# 56_ch_sample-and-hold_card_v1_2.net
KiCad netlist of a schematic drawn in EAGLE
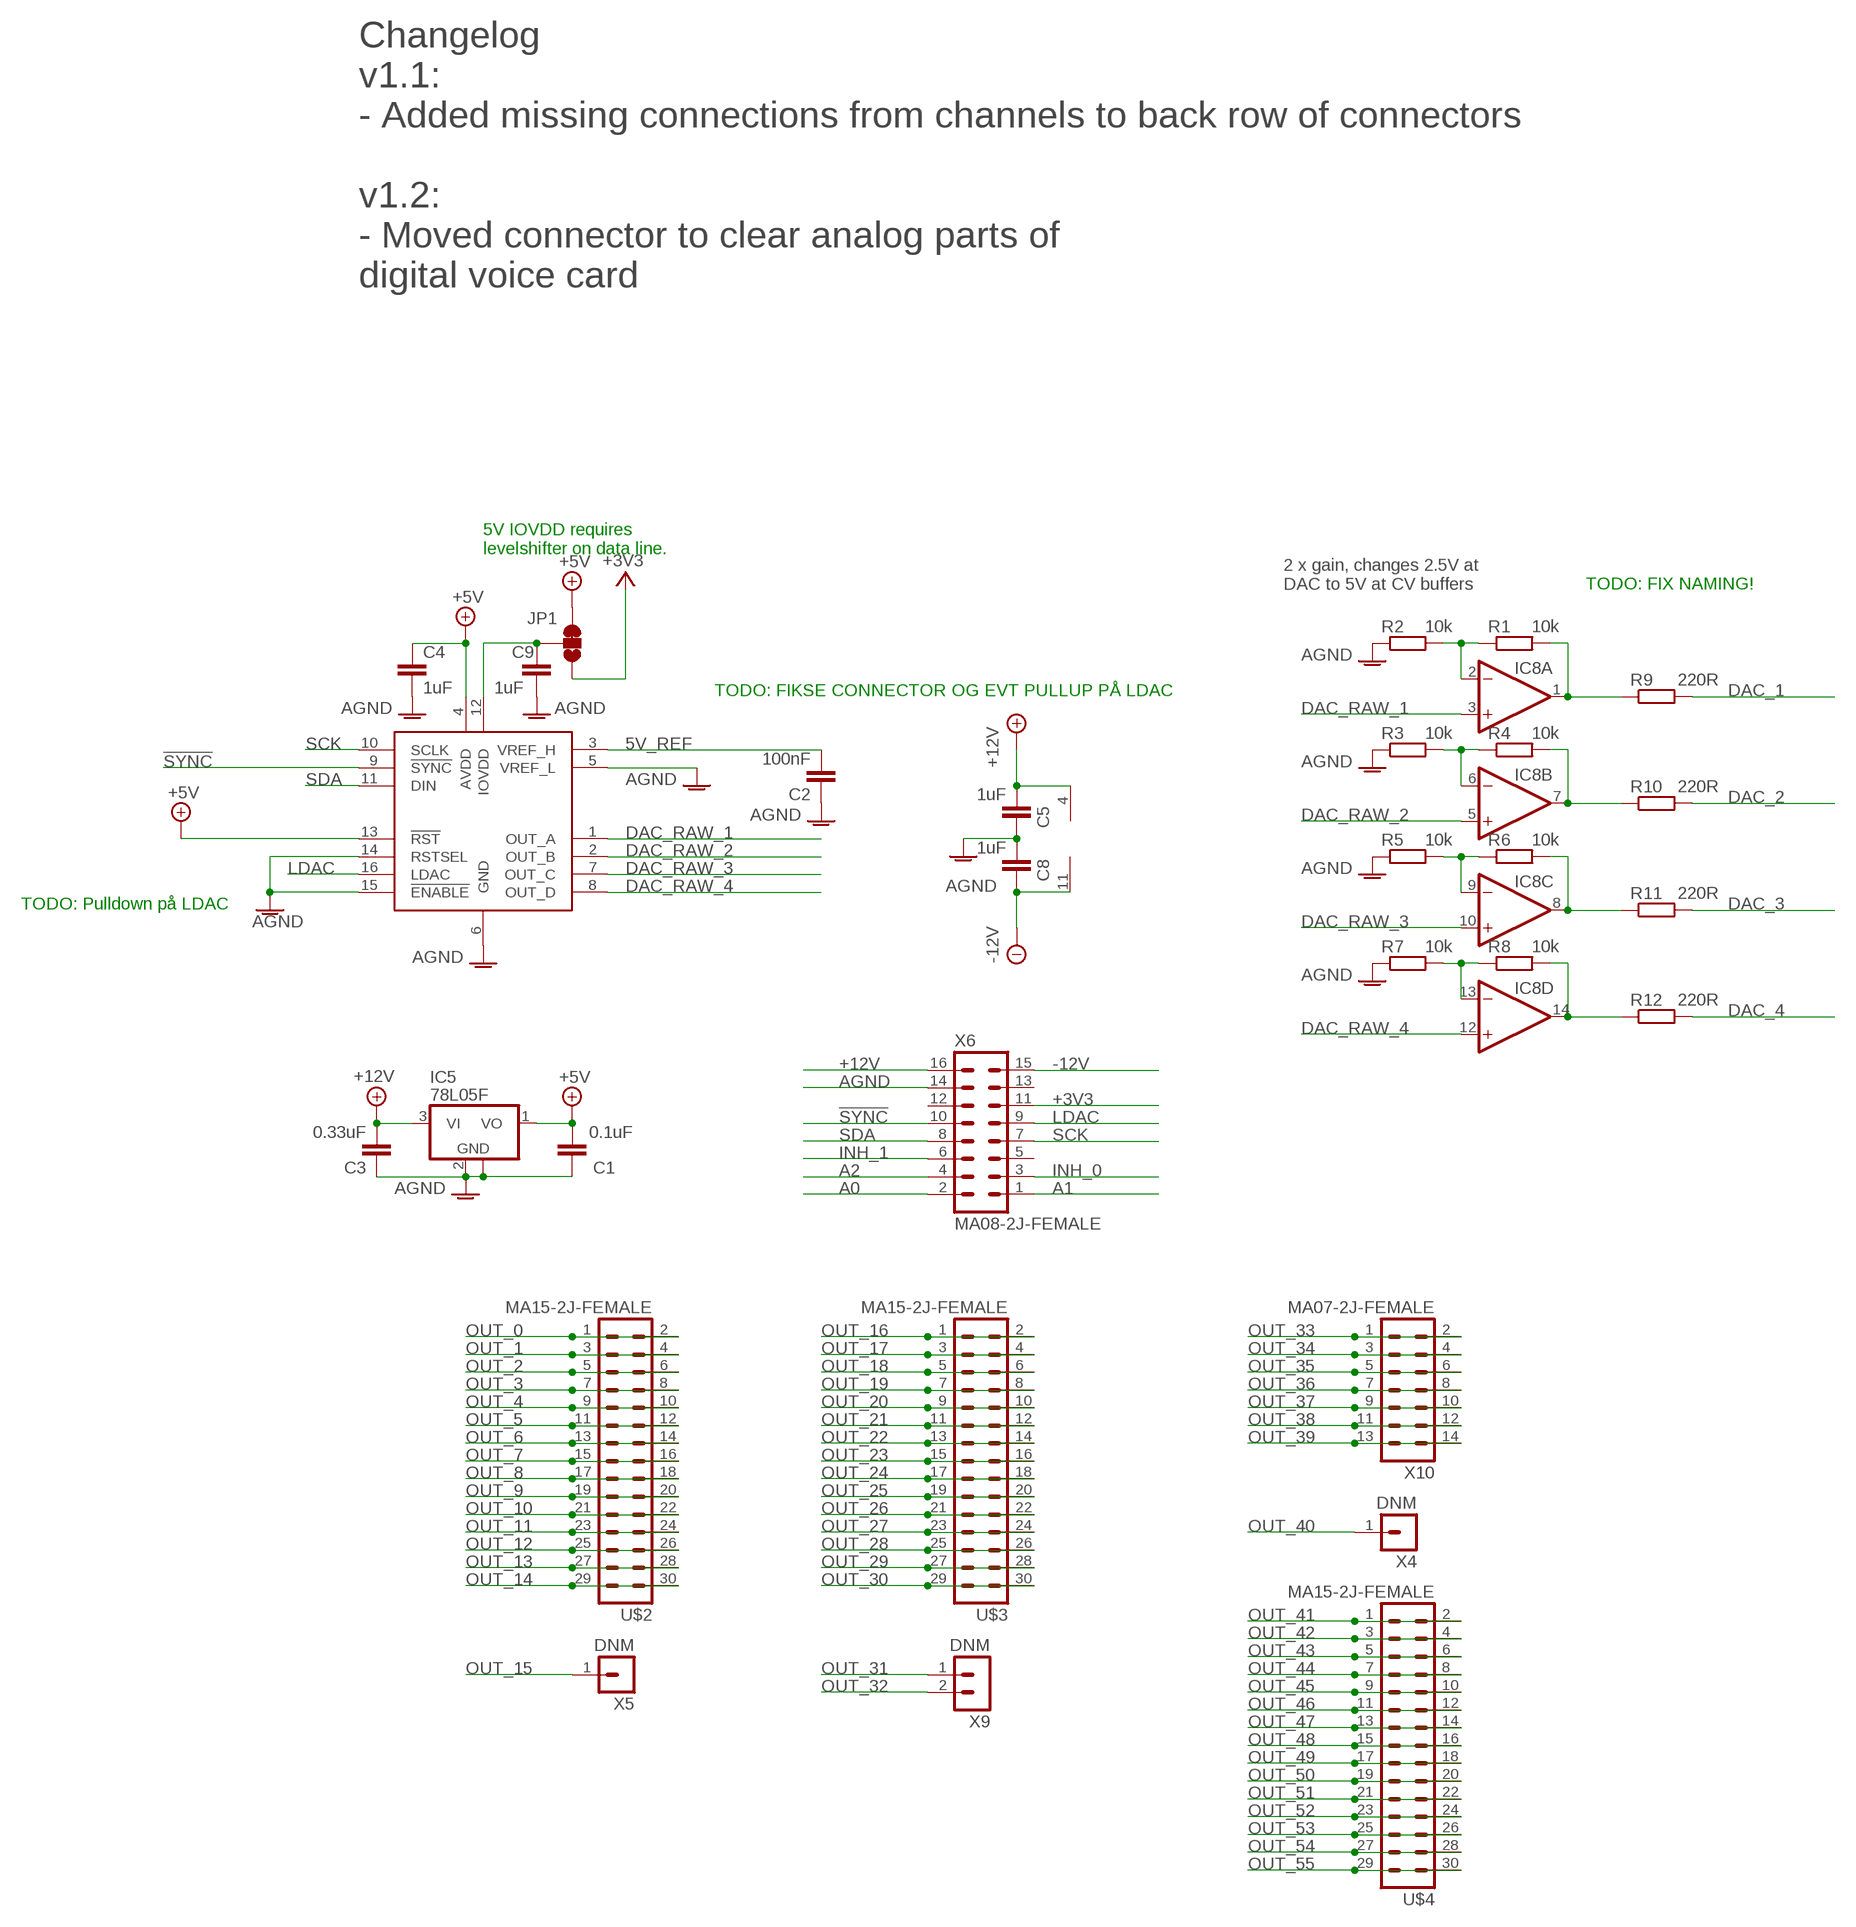
[diagram p0: schematic, sheet 1]
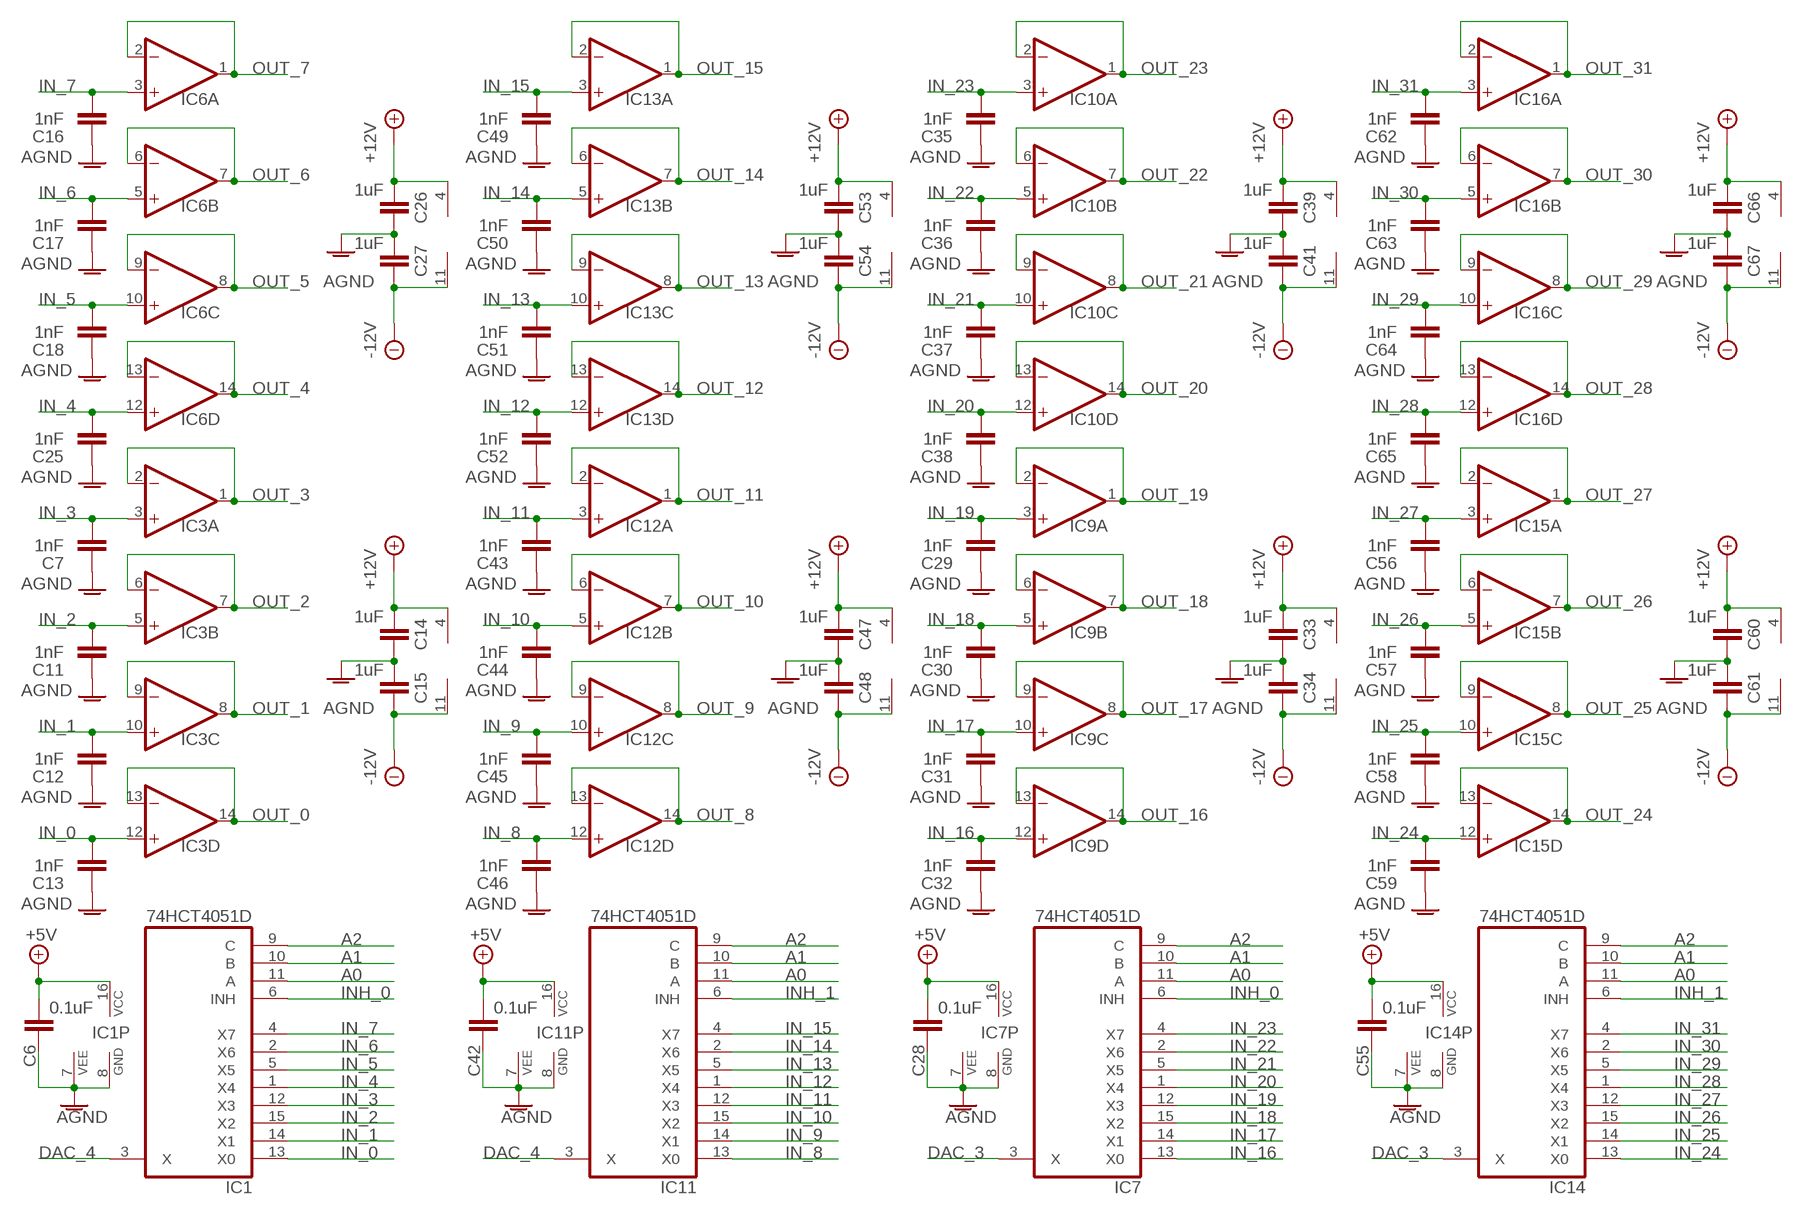
[diagram p1: schematic, sheet 2]
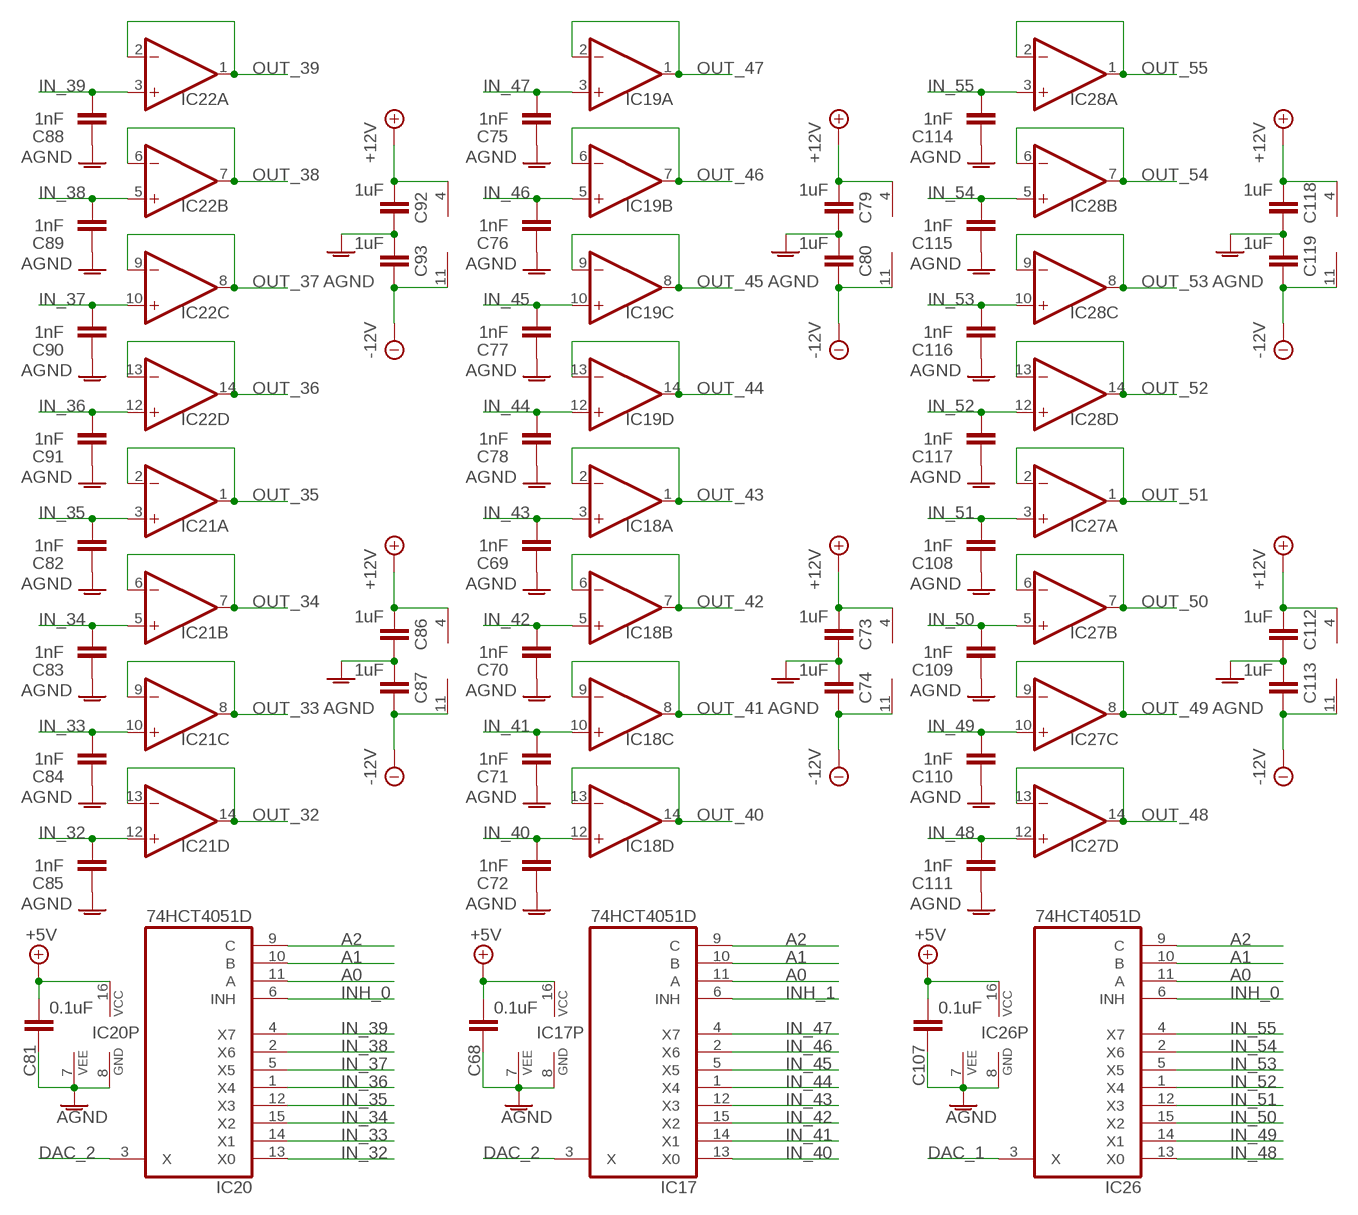
[diagram p2: schematic, sheet 3]

(export (version "E")
  (design (tool "Eeschema 10.0.6"))
  (components
    (comp (ref "C1")
      (value "0.1uF")
      (footprint "eagle-import:C0603")
      (libsource (lib "eagle-import") (part "C-EUC0603"))
    )
    (comp (ref "C2")
      (value "100nF")
      (footprint "eagle-import:C0603")
      (libsource (lib "eagle-import") (part "C-EUC0603"))
    )
    (comp (ref "C3")
      (value "0.33uF")
      (footprint "eagle-import:C0603")
      (libsource (lib "eagle-import") (part "C-EUC0603"))
    )
    (comp (ref "C4")
      (value "1uF")
      (footprint "eagle-import:C0402-J")
      (libsource (lib "eagle-import") (part "C-EU-J0402"))
    )
    (comp (ref "C5")
      (value "1uF")
      (footprint "eagle-import:C0402-J")
      (libsource (lib "eagle-import") (part "C-EU-J0402"))
    )
    (comp (ref "C8")
      (value "1uF")
      (footprint "eagle-import:C0402-J")
      (libsource (lib "eagle-import") (part "C-EU-J0402"))
    )
    (comp (ref "C9")
      (value "1uF")
      (footprint "eagle-import:C0402-J")
      (libsource (lib "eagle-import") (part "C-EU-J0402"))
    )
    (comp (ref "IC2")
      (value "DAC8565F")
      (footprint "eagle-import:DIL16-FM-CON")
      (libsource (lib "eagle-import") (part "DAC8565F"))
    )
    (comp (ref "IC5")
      (value "78L05F")
      (footprint "eagle-import:SOT89")
      (libsource (lib "eagle-import") (part "78LF05"))
    )
    (comp (ref "IC8")
      (value "TL074JT")
      (footprint "eagle-import:TSSOP14J")
      (libsource (lib "eagle-import") (part "TL074JT"))
    )
    (comp (ref "JP1")
      (value "JUMPER-SMT_3_1-NC_TRACE_NO-SILK_DNM")
      (footprint "eagle-import:SMT-JUMPER_3_1-NC_TRACE_NO-SILK")
      (libsource (lib "eagle-import") (part "JUMPER-SMT_3_1-NC_TRACE_NO-SILK"))
    )
    (comp (ref "R1")
      (value "10k")
      (footprint "eagle-import:R0603")
      (libsource (lib "eagle-import") (part "R-EU_R0603"))
    )
    (comp (ref "R2")
      (value "10k")
      (footprint "eagle-import:R0603")
      (libsource (lib "eagle-import") (part "R-EU_R0603"))
    )
    (comp (ref "R3")
      (value "10k")
      (footprint "eagle-import:R0603")
      (libsource (lib "eagle-import") (part "R-EU_R0603"))
    )
    (comp (ref "R4")
      (value "10k")
      (footprint "eagle-import:R0603")
      (libsource (lib "eagle-import") (part "R-EU_R0603"))
    )
    (comp (ref "R5")
      (value "10k")
      (footprint "eagle-import:R0603")
      (libsource (lib "eagle-import") (part "R-EU_R0603"))
    )
    (comp (ref "R6")
      (value "10k")
      (footprint "eagle-import:R0603")
      (libsource (lib "eagle-import") (part "R-EU_R0603"))
    )
    (comp (ref "R7")
      (value "10k")
      (footprint "eagle-import:R0603")
      (libsource (lib "eagle-import") (part "R-EU_R0603"))
    )
    (comp (ref "R8")
      (value "10k")
      (footprint "eagle-import:R0603")
      (libsource (lib "eagle-import") (part "R-EU_R0603"))
    )
    (comp (ref "R9")
      (value "220R")
      (footprint "eagle-import:R0603")
      (libsource (lib "eagle-import") (part "R-EU_R0603"))
    )
    (comp (ref "R10")
      (value "220R")
      (footprint "eagle-import:R0603")
      (libsource (lib "eagle-import") (part "R-EU_R0603"))
    )
    (comp (ref "R11")
      (value "220R")
      (footprint "eagle-import:R0603")
      (libsource (lib "eagle-import") (part "R-EU_R0603"))
    )
    (comp (ref "R12")
      (value "220R")
      (footprint "eagle-import:R0603")
      (libsource (lib "eagle-import") (part "R-EU_R0603"))
    )
    (comp (ref "U$2")
      (value "MA15-2J-FEMALE")
      (footprint "eagle-import:MA15-2J")
      (libsource (lib "eagle-import") (part "MA15-2J"))
    )
    (comp (ref "U$3")
      (value "MA15-2J-FEMALE")
      (footprint "eagle-import:MA15-2J")
      (libsource (lib "eagle-import") (part "MA15-2J"))
    )
    (comp (ref "U$4")
      (value "MA15-2J-FEMALE")
      (footprint "eagle-import:MA15-2J")
      (libsource (lib "eagle-import") (part "MA15-2J"))
    )
    (comp (ref "X4")
      (value "DNM")
      (footprint "eagle-import:MA01N-1J")
      (libsource (lib "eagle-import") (part "MA01-1JN"))
    )
    (comp (ref "X5")
      (value "DNM")
      (footprint "eagle-import:MA01N-1J")
      (libsource (lib "eagle-import") (part "MA01-1JN"))
    )
    (comp (ref "X6")
      (value "MA08-2J-FEMALE")
      (footprint "eagle-import:MA08-2J")
      (libsource (lib "eagle-import") (part "MA08-2J"))
    )
    (comp (ref "X9")
      (value "DNM")
      (footprint "eagle-import:MA02N-1J")
      (libsource (lib "eagle-import") (part "MA02-1JN"))
    )
    (comp (ref "X10")
      (value "MA07-2J-FEMALE")
      (footprint "eagle-import:MA07-2J")
      (libsource (lib "eagle-import") (part "MA07-2J"))
    )
    (comp (ref "C68")
      (value "0.1uF")
      (footprint "eagle-import:C0402-J")
      (libsource (lib "eagle-import") (part "C-EU-J0402"))
    )
    (comp (ref "C69")
      (value "1nF")
      (footprint "eagle-import:C0603-J")
      (libsource (lib "eagle-import") (part "C-EU-J0603"))
    )
    (comp (ref "C70")
      (value "1nF")
      (footprint "eagle-import:C0603-J")
      (libsource (lib "eagle-import") (part "C-EU-J0603"))
    )
    (comp (ref "C71")
      (value "1nF")
      (footprint "eagle-import:C0603-J")
      (libsource (lib "eagle-import") (part "C-EU-J0603"))
    )
    (comp (ref "C72")
      (value "1nF")
      (footprint "eagle-import:C0603-J")
      (libsource (lib "eagle-import") (part "C-EU-J0603"))
    )
    (comp (ref "C73")
      (value "1uF")
      (footprint "eagle-import:C0402-J")
      (libsource (lib "eagle-import") (part "C-EU-J0402"))
    )
    (comp (ref "C74")
      (value "1uF")
      (footprint "eagle-import:C0402-J")
      (libsource (lib "eagle-import") (part "C-EU-J0402"))
    )
    (comp (ref "C75")
      (value "1nF")
      (footprint "eagle-import:C0603-J")
      (libsource (lib "eagle-import") (part "C-EU-J0603"))
    )
    (comp (ref "C76")
      (value "1nF")
      (footprint "eagle-import:C0603-J")
      (libsource (lib "eagle-import") (part "C-EU-J0603"))
    )
    (comp (ref "C77")
      (value "1nF")
      (footprint "eagle-import:C0603-J")
      (libsource (lib "eagle-import") (part "C-EU-J0603"))
    )
    (comp (ref "C78")
      (value "1nF")
      (footprint "eagle-import:C0603-J")
      (libsource (lib "eagle-import") (part "C-EU-J0603"))
    )
    (comp (ref "C79")
      (value "1uF")
      (footprint "eagle-import:C0402-J")
      (libsource (lib "eagle-import") (part "C-EU-J0402"))
    )
    (comp (ref "C80")
      (value "1uF")
      (footprint "eagle-import:C0402-J")
      (libsource (lib "eagle-import") (part "C-EU-J0402"))
    )
    (comp (ref "C81")
      (value "0.1uF")
      (footprint "eagle-import:C0402-J")
      (libsource (lib "eagle-import") (part "C-EU-J0402"))
    )
    (comp (ref "C82")
      (value "1nF")
      (footprint "eagle-import:C0603-J")
      (libsource (lib "eagle-import") (part "C-EU-J0603"))
    )
    (comp (ref "C83")
      (value "1nF")
      (footprint "eagle-import:C0603-J")
      (libsource (lib "eagle-import") (part "C-EU-J0603"))
    )
    (comp (ref "C84")
      (value "1nF")
      (footprint "eagle-import:C0603-J")
      (libsource (lib "eagle-import") (part "C-EU-J0603"))
    )
    (comp (ref "C85")
      (value "1nF")
      (footprint "eagle-import:C0603-J")
      (libsource (lib "eagle-import") (part "C-EU-J0603"))
    )
    (comp (ref "C86")
      (value "1uF")
      (footprint "eagle-import:C0402-J")
      (libsource (lib "eagle-import") (part "C-EU-J0402"))
    )
    (comp (ref "C87")
      (value "1uF")
      (footprint "eagle-import:C0402-J")
      (libsource (lib "eagle-import") (part "C-EU-J0402"))
    )
    (comp (ref "C88")
      (value "1nF")
      (footprint "eagle-import:C0603-J")
      (libsource (lib "eagle-import") (part "C-EU-J0603"))
    )
    (comp (ref "C89")
      (value "1nF")
      (footprint "eagle-import:C0603-J")
      (libsource (lib "eagle-import") (part "C-EU-J0603"))
    )
    (comp (ref "C90")
      (value "1nF")
      (footprint "eagle-import:C0603-J")
      (libsource (lib "eagle-import") (part "C-EU-J0603"))
    )
    (comp (ref "C91")
      (value "1nF")
      (footprint "eagle-import:C0603-J")
      (libsource (lib "eagle-import") (part "C-EU-J0603"))
    )
    (comp (ref "C92")
      (value "1uF")
      (footprint "eagle-import:C0402-J")
      (libsource (lib "eagle-import") (part "C-EU-J0402"))
    )
    (comp (ref "C93")
      (value "1uF")
      (footprint "eagle-import:C0402-J")
      (libsource (lib "eagle-import") (part "C-EU-J0402"))
    )
    (comp (ref "C107")
      (value "0.1uF")
      (footprint "eagle-import:C0402-J")
      (libsource (lib "eagle-import") (part "C-EU-J0402"))
    )
    (comp (ref "C108")
      (value "1nF")
      (footprint "eagle-import:C0603-J")
      (libsource (lib "eagle-import") (part "C-EU-J0603"))
    )
    (comp (ref "C109")
      (value "1nF")
      (footprint "eagle-import:C0603-J")
      (libsource (lib "eagle-import") (part "C-EU-J0603"))
    )
    (comp (ref "C110")
      (value "1nF")
      (footprint "eagle-import:C0603-J")
      (libsource (lib "eagle-import") (part "C-EU-J0603"))
    )
    (comp (ref "C111")
      (value "1nF")
      (footprint "eagle-import:C0603-J")
      (libsource (lib "eagle-import") (part "C-EU-J0603"))
    )
    (comp (ref "C112")
      (value "1uF")
      (footprint "eagle-import:C0402-J")
      (libsource (lib "eagle-import") (part "C-EU-J0402"))
    )
    (comp (ref "C113")
      (value "1uF")
      (footprint "eagle-import:C0402-J")
      (libsource (lib "eagle-import") (part "C-EU-J0402"))
    )
    (comp (ref "C114")
      (value "1nF")
      (footprint "eagle-import:C0603-J")
      (libsource (lib "eagle-import") (part "C-EU-J0603"))
    )
    (comp (ref "C115")
      (value "1nF")
      (footprint "eagle-import:C0603-J")
      (libsource (lib "eagle-import") (part "C-EU-J0603"))
    )
    (comp (ref "C116")
      (value "1nF")
      (footprint "eagle-import:C0603-J")
      (libsource (lib "eagle-import") (part "C-EU-J0603"))
    )
    (comp (ref "C117")
      (value "1nF")
      (footprint "eagle-import:C0603-J")
      (libsource (lib "eagle-import") (part "C-EU-J0603"))
    )
    (comp (ref "C118")
      (value "1uF")
      (footprint "eagle-import:C0402-J")
      (libsource (lib "eagle-import") (part "C-EU-J0402"))
    )
    (comp (ref "C119")
      (value "1uF")
      (footprint "eagle-import:C0402-J")
      (libsource (lib "eagle-import") (part "C-EU-J0402"))
    )
    (comp (ref "IC17")
      (value "74HCT4051D")
      (footprint "eagle-import:SO16")
      (libsource (lib "eagle-import") (part "4051D"))
    )
    (comp (ref "IC18")
      (value "TL074JT")
      (footprint "eagle-import:TSSOP14J")
      (libsource (lib "eagle-import") (part "TL074JT"))
    )
    (comp (ref "IC19")
      (value "TL074JT")
      (footprint "eagle-import:TSSOP14J")
      (libsource (lib "eagle-import") (part "TL074JT"))
    )
    (comp (ref "IC20")
      (value "74HCT4051D")
      (footprint "eagle-import:SO16")
      (libsource (lib "eagle-import") (part "4051D"))
    )
    (comp (ref "IC21")
      (value "TL074JT")
      (footprint "eagle-import:TSSOP14J")
      (libsource (lib "eagle-import") (part "TL074JT"))
    )
    (comp (ref "IC22")
      (value "TL074JT")
      (footprint "eagle-import:TSSOP14J")
      (libsource (lib "eagle-import") (part "TL074JT"))
    )
    (comp (ref "IC26")
      (value "74HCT4051D")
      (footprint "eagle-import:SO16")
      (libsource (lib "eagle-import") (part "4051D"))
    )
    (comp (ref "IC27")
      (value "TL074JT")
      (footprint "eagle-import:TSSOP14J")
      (libsource (lib "eagle-import") (part "TL074JT"))
    )
    (comp (ref "IC28")
      (value "TL074JT")
      (footprint "eagle-import:TSSOP14J")
      (libsource (lib "eagle-import") (part "TL074JT"))
    )
    (comp (ref "C6")
      (value "0.1uF")
      (footprint "eagle-import:C0402-J")
      (libsource (lib "eagle-import") (part "C-EU-J0402"))
    )
    (comp (ref "C7")
      (value "1nF")
      (footprint "eagle-import:C0603-J")
      (libsource (lib "eagle-import") (part "C-EU-J0603"))
    )
    (comp (ref "C11")
      (value "1nF")
      (footprint "eagle-import:C0603-J")
      (libsource (lib "eagle-import") (part "C-EU-J0603"))
    )
    (comp (ref "C12")
      (value "1nF")
      (footprint "eagle-import:C0603-J")
      (libsource (lib "eagle-import") (part "C-EU-J0603"))
    )
    (comp (ref "C13")
      (value "1nF")
      (footprint "eagle-import:C0603-J")
      (libsource (lib "eagle-import") (part "C-EU-J0603"))
    )
    (comp (ref "C14")
      (value "1uF")
      (footprint "eagle-import:C0402-J")
      (libsource (lib "eagle-import") (part "C-EU-J0402"))
    )
    (comp (ref "C15")
      (value "1uF")
      (footprint "eagle-import:C0402-J")
      (libsource (lib "eagle-import") (part "C-EU-J0402"))
    )
    (comp (ref "C16")
      (value "1nF")
      (footprint "eagle-import:C0603-J")
      (libsource (lib "eagle-import") (part "C-EU-J0603"))
    )
    (comp (ref "C17")
      (value "1nF")
      (footprint "eagle-import:C0603-J")
      (libsource (lib "eagle-import") (part "C-EU-J0603"))
    )
    (comp (ref "C18")
      (value "1nF")
      (footprint "eagle-import:C0603-J")
      (libsource (lib "eagle-import") (part "C-EU-J0603"))
    )
    (comp (ref "C25")
      (value "1nF")
      (footprint "eagle-import:C0603-J")
      (libsource (lib "eagle-import") (part "C-EU-J0603"))
    )
    (comp (ref "C26")
      (value "1uF")
      (footprint "eagle-import:C0402-J")
      (libsource (lib "eagle-import") (part "C-EU-J0402"))
    )
    (comp (ref "C27")
      (value "1uF")
      (footprint "eagle-import:C0402-J")
      (libsource (lib "eagle-import") (part "C-EU-J0402"))
    )
    (comp (ref "C28")
      (value "0.1uF")
      (footprint "eagle-import:C0402-J")
      (libsource (lib "eagle-import") (part "C-EU-J0402"))
    )
    (comp (ref "C29")
      (value "1nF")
      (footprint "eagle-import:C0603-J")
      (libsource (lib "eagle-import") (part "C-EU-J0603"))
    )
    (comp (ref "C30")
      (value "1nF")
      (footprint "eagle-import:C0603-J")
      (libsource (lib "eagle-import") (part "C-EU-J0603"))
    )
    (comp (ref "C31")
      (value "1nF")
      (footprint "eagle-import:C0603-J")
      (libsource (lib "eagle-import") (part "C-EU-J0603"))
    )
    (comp (ref "C32")
      (value "1nF")
      (footprint "eagle-import:C0603-J")
      (libsource (lib "eagle-import") (part "C-EU-J0603"))
    )
    (comp (ref "C33")
      (value "1uF")
      (footprint "eagle-import:C0402-J")
      (libsource (lib "eagle-import") (part "C-EU-J0402"))
    )
    (comp (ref "C34")
      (value "1uF")
      (footprint "eagle-import:C0402-J")
      (libsource (lib "eagle-import") (part "C-EU-J0402"))
    )
    (comp (ref "C35")
      (value "1nF")
      (footprint "eagle-import:C0603-J")
      (libsource (lib "eagle-import") (part "C-EU-J0603"))
    )
    (comp (ref "C36")
      (value "1nF")
      (footprint "eagle-import:C0603-J")
      (libsource (lib "eagle-import") (part "C-EU-J0603"))
    )
    (comp (ref "C37")
      (value "1nF")
      (footprint "eagle-import:C0603-J")
      (libsource (lib "eagle-import") (part "C-EU-J0603"))
    )
    (comp (ref "C38")
      (value "1nF")
      (footprint "eagle-import:C0603-J")
      (libsource (lib "eagle-import") (part "C-EU-J0603"))
    )
    (comp (ref "C39")
      (value "1uF")
      (footprint "eagle-import:C0402-J")
      (libsource (lib "eagle-import") (part "C-EU-J0402"))
    )
    (comp (ref "C41")
      (value "1uF")
      (footprint "eagle-import:C0402-J")
      (libsource (lib "eagle-import") (part "C-EU-J0402"))
    )
    (comp (ref "C42")
      (value "0.1uF")
      (footprint "eagle-import:C0402-J")
      (libsource (lib "eagle-import") (part "C-EU-J0402"))
    )
    (comp (ref "C43")
      (value "1nF")
      (footprint "eagle-import:C0603-J")
      (libsource (lib "eagle-import") (part "C-EU-J0603"))
    )
    (comp (ref "C44")
      (value "1nF")
      (footprint "eagle-import:C0603-J")
      (libsource (lib "eagle-import") (part "C-EU-J0603"))
    )
    (comp (ref "C45")
      (value "1nF")
      (footprint "eagle-import:C0603-J")
      (libsource (lib "eagle-import") (part "C-EU-J0603"))
    )
    (comp (ref "C46")
      (value "1nF")
      (footprint "eagle-import:C0603-J")
      (libsource (lib "eagle-import") (part "C-EU-J0603"))
    )
    (comp (ref "C47")
      (value "1uF")
      (footprint "eagle-import:C0402-J")
      (libsource (lib "eagle-import") (part "C-EU-J0402"))
    )
    (comp (ref "C48")
      (value "1uF")
      (footprint "eagle-import:C0402-J")
      (libsource (lib "eagle-import") (part "C-EU-J0402"))
    )
    (comp (ref "C49")
      (value "1nF")
      (footprint "eagle-import:C0603-J")
      (libsource (lib "eagle-import") (part "C-EU-J0603"))
    )
    (comp (ref "C50")
      (value "1nF")
      (footprint "eagle-import:C0603-J")
      (libsource (lib "eagle-import") (part "C-EU-J0603"))
    )
    (comp (ref "C51")
      (value "1nF")
      (footprint "eagle-import:C0603-J")
      (libsource (lib "eagle-import") (part "C-EU-J0603"))
    )
    (comp (ref "C52")
      (value "1nF")
      (footprint "eagle-import:C0603-J")
      (libsource (lib "eagle-import") (part "C-EU-J0603"))
    )
    (comp (ref "C53")
      (value "1uF")
      (footprint "eagle-import:C0402-J")
      (libsource (lib "eagle-import") (part "C-EU-J0402"))
    )
    (comp (ref "C54")
      (value "1uF")
      (footprint "eagle-import:C0402-J")
      (libsource (lib "eagle-import") (part "C-EU-J0402"))
    )
    (comp (ref "C55")
      (value "0.1uF")
      (footprint "eagle-import:C0402-J")
      (libsource (lib "eagle-import") (part "C-EU-J0402"))
    )
    (comp (ref "C56")
      (value "1nF")
      (footprint "eagle-import:C0603-J")
      (libsource (lib "eagle-import") (part "C-EU-J0603"))
    )
    (comp (ref "C57")
      (value "1nF")
      (footprint "eagle-import:C0603-J")
      (libsource (lib "eagle-import") (part "C-EU-J0603"))
    )
    (comp (ref "C58")
      (value "1nF")
      (footprint "eagle-import:C0603-J")
      (libsource (lib "eagle-import") (part "C-EU-J0603"))
    )
    (comp (ref "C59")
      (value "1nF")
      (footprint "eagle-import:C0603-J")
      (libsource (lib "eagle-import") (part "C-EU-J0603"))
    )
    (comp (ref "C60")
      (value "1uF")
      (footprint "eagle-import:C0402-J")
      (libsource (lib "eagle-import") (part "C-EU-J0402"))
    )
    (comp (ref "C61")
      (value "1uF")
      (footprint "eagle-import:C0402-J")
      (libsource (lib "eagle-import") (part "C-EU-J0402"))
    )
    (comp (ref "C62")
      (value "1nF")
      (footprint "eagle-import:C0603-J")
      (libsource (lib "eagle-import") (part "C-EU-J0603"))
    )
    (comp (ref "C63")
      (value "1nF")
      (footprint "eagle-import:C0603-J")
      (libsource (lib "eagle-import") (part "C-EU-J0603"))
    )
    (comp (ref "C64")
      (value "1nF")
      (footprint "eagle-import:C0603-J")
      (libsource (lib "eagle-import") (part "C-EU-J0603"))
    )
    (comp (ref "C65")
      (value "1nF")
      (footprint "eagle-import:C0603-J")
      (libsource (lib "eagle-import") (part "C-EU-J0603"))
    )
    (comp (ref "C66")
      (value "1uF")
      (footprint "eagle-import:C0402-J")
      (libsource (lib "eagle-import") (part "C-EU-J0402"))
    )
    (comp (ref "C67")
      (value "1uF")
      (footprint "eagle-import:C0402-J")
      (libsource (lib "eagle-import") (part "C-EU-J0402"))
    )
    (comp (ref "IC1")
      (value "74HCT4051D")
      (footprint "eagle-import:SO16")
      (libsource (lib "eagle-import") (part "4051D"))
    )
    (comp (ref "IC3")
      (value "TL074JT")
      (footprint "eagle-import:TSSOP14J")
      (libsource (lib "eagle-import") (part "TL074JT"))
    )
    (comp (ref "IC6")
      (value "TL074JT")
      (footprint "eagle-import:TSSOP14J")
      (libsource (lib "eagle-import") (part "TL074JT"))
    )
    (comp (ref "IC7")
      (value "74HCT4051D")
      (footprint "eagle-import:SO16")
      (libsource (lib "eagle-import") (part "4051D"))
    )
    (comp (ref "IC9")
      (value "TL074JT")
      (footprint "eagle-import:TSSOP14J")
      (libsource (lib "eagle-import") (part "TL074JT"))
    )
    (comp (ref "IC10")
      (value "TL074JT")
      (footprint "eagle-import:TSSOP14J")
      (libsource (lib "eagle-import") (part "TL074JT"))
    )
    (comp (ref "IC11")
      (value "74HCT4051D")
      (footprint "eagle-import:SO16")
      (libsource (lib "eagle-import") (part "4051D"))
    )
    (comp (ref "IC12")
      (value "TL074JT")
      (footprint "eagle-import:TSSOP14J")
      (libsource (lib "eagle-import") (part "TL074JT"))
    )
    (comp (ref "IC13")
      (value "TL074JT")
      (footprint "eagle-import:TSSOP14J")
      (libsource (lib "eagle-import") (part "TL074JT"))
    )
    (comp (ref "IC14")
      (value "74HCT4051D")
      (footprint "eagle-import:SO16")
      (libsource (lib "eagle-import") (part "4051D"))
    )
    (comp (ref "IC15")
      (value "TL074JT")
      (footprint "eagle-import:TSSOP14J")
      (libsource (lib "eagle-import") (part "TL074JT"))
    )
    (comp (ref "IC16")
      (value "TL074JT")
      (footprint "eagle-import:TSSOP14J")
      (libsource (lib "eagle-import") (part "TL074JT"))
    )
  )
  (nets
    (net (code "1") (name "+3V3") (class "Default")
      (node (ref "JP1") (pin "1") (pinfunction "1_1") (pintype "passive"))
      (node (ref "X6") (pin "11") (pinfunction "11_11") (pintype "passive"))
    )
    (net (code "2") (name "+5V") (class "Default")
      (node (ref "C1") (pin "2") (pinfunction "2_2") (pintype "passive"))
      (node (ref "C107") (pin "2") (pinfunction "2_2") (pintype "passive"))
      (node (ref "C28") (pin "2") (pinfunction "2_2") (pintype "passive"))
      (node (ref "C4") (pin "1") (pinfunction "1_1") (pintype "passive"))
      (node (ref "C42") (pin "2") (pinfunction "2_2") (pintype "passive"))
      (node (ref "C55") (pin "2") (pinfunction "2_2") (pintype "passive"))
      (node (ref "C6") (pin "2") (pinfunction "2_2") (pintype "passive"))
      (node (ref "C68") (pin "2") (pinfunction "2_2") (pintype "passive"))
      (node (ref "C81") (pin "2") (pinfunction "2_2") (pintype "passive"))
      (node (ref "IC1") (pin "16") (pinfunction "VCC_16") (pintype "power_in"))
      (node (ref "IC11") (pin "16") (pinfunction "VCC_16") (pintype "power_in"))
      (node (ref "IC14") (pin "16") (pinfunction "VCC_16") (pintype "power_in"))
      (node (ref "IC17") (pin "16") (pinfunction "VCC_16") (pintype "power_in"))
      (node (ref "IC2") (pin "13") (pinfunction "~{RST}_13") (pintype "bidirectional"))
      (node (ref "IC2") (pin "4") (pinfunction "AVDD_4") (pintype "power_in"))
      (node (ref "IC20") (pin "16") (pinfunction "VCC_16") (pintype "power_in"))
      (node (ref "IC26") (pin "16") (pinfunction "VCC_16") (pintype "power_in"))
      (node (ref "IC5") (pin "1") (pinfunction "VO_1") (pintype "passive"))
      (node (ref "IC7") (pin "16") (pinfunction "VCC_16") (pintype "power_in"))
      (node (ref "JP1") (pin "3") (pinfunction "3_3") (pintype "passive"))
    )
    (net (code "3") (name "+12V") (class "Default")
      (node (ref "C112") (pin "1") (pinfunction "1_1") (pintype "passive"))
      (node (ref "C118") (pin "1") (pinfunction "1_1") (pintype "passive"))
      (node (ref "C14") (pin "1") (pinfunction "1_1") (pintype "passive"))
      (node (ref "C26") (pin "1") (pinfunction "1_1") (pintype "passive"))
      (node (ref "C3") (pin "2") (pinfunction "2_2") (pintype "passive"))
      (node (ref "C33") (pin "1") (pinfunction "1_1") (pintype "passive"))
      (node (ref "C39") (pin "1") (pinfunction "1_1") (pintype "passive"))
      (node (ref "C47") (pin "1") (pinfunction "1_1") (pintype "passive"))
      (node (ref "C5") (pin "1") (pinfunction "1_1") (pintype "passive"))
      (node (ref "C53") (pin "1") (pinfunction "1_1") (pintype "passive"))
      (node (ref "C60") (pin "1") (pinfunction "1_1") (pintype "passive"))
      (node (ref "C66") (pin "1") (pinfunction "1_1") (pintype "passive"))
      (node (ref "C73") (pin "1") (pinfunction "1_1") (pintype "passive"))
      (node (ref "C79") (pin "1") (pinfunction "1_1") (pintype "passive"))
      (node (ref "C86") (pin "1") (pinfunction "1_1") (pintype "passive"))
      (node (ref "C92") (pin "1") (pinfunction "1_1") (pintype "passive"))
      (node (ref "IC10") (pin "4") (pinfunction "V+_4") (pintype "power_in"))
      (node (ref "IC12") (pin "4") (pinfunction "V+_4") (pintype "power_in"))
      (node (ref "IC13") (pin "4") (pinfunction "V+_4") (pintype "power_in"))
      (node (ref "IC15") (pin "4") (pinfunction "V+_4") (pintype "power_in"))
      (node (ref "IC16") (pin "4") (pinfunction "V+_4") (pintype "power_in"))
      (node (ref "IC18") (pin "4") (pinfunction "V+_4") (pintype "power_in"))
      (node (ref "IC19") (pin "4") (pinfunction "V+_4") (pintype "power_in"))
      (node (ref "IC21") (pin "4") (pinfunction "V+_4") (pintype "power_in"))
      (node (ref "IC22") (pin "4") (pinfunction "V+_4") (pintype "power_in"))
      (node (ref "IC27") (pin "4") (pinfunction "V+_4") (pintype "power_in"))
      (node (ref "IC28") (pin "4") (pinfunction "V+_4") (pintype "power_in"))
      (node (ref "IC3") (pin "4") (pinfunction "V+_4") (pintype "power_in"))
      (node (ref "IC5") (pin "3") (pinfunction "VI_3") (pintype "input"))
      (node (ref "IC6") (pin "4") (pinfunction "V+_4") (pintype "power_in"))
      (node (ref "IC8") (pin "4") (pinfunction "V+_4") (pintype "power_in"))
      (node (ref "IC9") (pin "4") (pinfunction "V+_4") (pintype "power_in"))
      (node (ref "X6") (pin "16") (pinfunction "16_16") (pintype "passive"))
    )
    (net (code "4") (name "-12V") (class "Default")
      (node (ref "C113") (pin "2") (pinfunction "2_2") (pintype "passive"))
      (node (ref "C119") (pin "2") (pinfunction "2_2") (pintype "passive"))
      (node (ref "C15") (pin "2") (pinfunction "2_2") (pintype "passive"))
      (node (ref "C27") (pin "2") (pinfunction "2_2") (pintype "passive"))
      (node (ref "C34") (pin "2") (pinfunction "2_2") (pintype "passive"))
      (node (ref "C41") (pin "2") (pinfunction "2_2") (pintype "passive"))
      (node (ref "C48") (pin "2") (pinfunction "2_2") (pintype "passive"))
      (node (ref "C54") (pin "2") (pinfunction "2_2") (pintype "passive"))
      (node (ref "C61") (pin "2") (pinfunction "2_2") (pintype "passive"))
      (node (ref "C67") (pin "2") (pinfunction "2_2") (pintype "passive"))
      (node (ref "C74") (pin "2") (pinfunction "2_2") (pintype "passive"))
      (node (ref "C8") (pin "2") (pinfunction "2_2") (pintype "passive"))
      (node (ref "C80") (pin "2") (pinfunction "2_2") (pintype "passive"))
      (node (ref "C87") (pin "2") (pinfunction "2_2") (pintype "passive"))
      (node (ref "C93") (pin "2") (pinfunction "2_2") (pintype "passive"))
      (node (ref "IC10") (pin "11") (pinfunction "V-_11") (pintype "power_in"))
      (node (ref "IC12") (pin "11") (pinfunction "V-_11") (pintype "power_in"))
      (node (ref "IC13") (pin "11") (pinfunction "V-_11") (pintype "power_in"))
      (node (ref "IC15") (pin "11") (pinfunction "V-_11") (pintype "power_in"))
      (node (ref "IC16") (pin "11") (pinfunction "V-_11") (pintype "power_in"))
      (node (ref "IC18") (pin "11") (pinfunction "V-_11") (pintype "power_in"))
      (node (ref "IC19") (pin "11") (pinfunction "V-_11") (pintype "power_in"))
      (node (ref "IC21") (pin "11") (pinfunction "V-_11") (pintype "power_in"))
      (node (ref "IC22") (pin "11") (pinfunction "V-_11") (pintype "power_in"))
      (node (ref "IC27") (pin "11") (pinfunction "V-_11") (pintype "power_in"))
      (node (ref "IC28") (pin "11") (pinfunction "V-_11") (pintype "power_in"))
      (node (ref "IC3") (pin "11") (pinfunction "V-_11") (pintype "power_in"))
      (node (ref "IC6") (pin "11") (pinfunction "V-_11") (pintype "power_in"))
      (node (ref "IC8") (pin "11") (pinfunction "V-_11") (pintype "power_in"))
      (node (ref "IC9") (pin "11") (pinfunction "V-_11") (pintype "power_in"))
      (node (ref "X6") (pin "15") (pinfunction "15_15") (pintype "passive"))
    )
    (net (code "5") (name "5V_REF") (class "Default")
      (node (ref "C2") (pin "2") (pinfunction "2_2") (pintype "passive"))
      (node (ref "IC2") (pin "3") (pinfunction "VREF_H_3") (pintype "bidirectional"))
    )
    (net (code "6") (name "A0") (class "Default")
      (node (ref "IC1") (pin "11") (pinfunction "A_11") (pintype "input"))
      (node (ref "IC11") (pin "11") (pinfunction "A_11") (pintype "input"))
      (node (ref "IC14") (pin "11") (pinfunction "A_11") (pintype "input"))
      (node (ref "IC17") (pin "11") (pinfunction "A_11") (pintype "input"))
      (node (ref "IC20") (pin "11") (pinfunction "A_11") (pintype "input"))
      (node (ref "IC26") (pin "11") (pinfunction "A_11") (pintype "input"))
      (node (ref "IC7") (pin "11") (pinfunction "A_11") (pintype "input"))
      (node (ref "X6") (pin "2") (pinfunction "2_2") (pintype "passive"))
    )
    (net (code "7") (name "A1") (class "Default")
      (node (ref "IC1") (pin "10") (pinfunction "B_10") (pintype "input"))
      (node (ref "IC11") (pin "10") (pinfunction "B_10") (pintype "input"))
      (node (ref "IC14") (pin "10") (pinfunction "B_10") (pintype "input"))
      (node (ref "IC17") (pin "10") (pinfunction "B_10") (pintype "input"))
      (node (ref "IC20") (pin "10") (pinfunction "B_10") (pintype "input"))
      (node (ref "IC26") (pin "10") (pinfunction "B_10") (pintype "input"))
      (node (ref "IC7") (pin "10") (pinfunction "B_10") (pintype "input"))
      (node (ref "X6") (pin "1") (pinfunction "1_1") (pintype "passive"))
    )
    (net (code "8") (name "A2") (class "Default")
      (node (ref "IC1") (pin "9") (pinfunction "C_9") (pintype "input"))
      (node (ref "IC11") (pin "9") (pinfunction "C_9") (pintype "input"))
      (node (ref "IC14") (pin "9") (pinfunction "C_9") (pintype "input"))
      (node (ref "IC17") (pin "9") (pinfunction "C_9") (pintype "input"))
      (node (ref "IC20") (pin "9") (pinfunction "C_9") (pintype "input"))
      (node (ref "IC26") (pin "9") (pinfunction "C_9") (pintype "input"))
      (node (ref "IC7") (pin "9") (pinfunction "C_9") (pintype "input"))
      (node (ref "X6") (pin "4") (pinfunction "4_4") (pintype "passive"))
    )
    (net (code "9") (name "AGND") (class "Default")
      (node (ref "C1") (pin "1") (pinfunction "1_1") (pintype "passive"))
      (node (ref "C107") (pin "1") (pinfunction "1_1") (pintype "passive"))
      (node (ref "C108") (pin "1") (pinfunction "1_1") (pintype "passive"))
      (node (ref "C109") (pin "1") (pinfunction "1_1") (pintype "passive"))
      (node (ref "C11") (pin "1") (pinfunction "1_1") (pintype "passive"))
      (node (ref "C110") (pin "1") (pinfunction "1_1") (pintype "passive"))
      (node (ref "C111") (pin "1") (pinfunction "1_1") (pintype "passive"))
      (node (ref "C112") (pin "2") (pinfunction "2_2") (pintype "passive"))
      (node (ref "C113") (pin "1") (pinfunction "1_1") (pintype "passive"))
      (node (ref "C114") (pin "1") (pinfunction "1_1") (pintype "passive"))
      (node (ref "C115") (pin "1") (pinfunction "1_1") (pintype "passive"))
      (node (ref "C116") (pin "1") (pinfunction "1_1") (pintype "passive"))
      (node (ref "C117") (pin "1") (pinfunction "1_1") (pintype "passive"))
      (node (ref "C118") (pin "2") (pinfunction "2_2") (pintype "passive"))
      (node (ref "C119") (pin "1") (pinfunction "1_1") (pintype "passive"))
      (node (ref "C12") (pin "1") (pinfunction "1_1") (pintype "passive"))
      (node (ref "C13") (pin "1") (pinfunction "1_1") (pintype "passive"))
      (node (ref "C14") (pin "2") (pinfunction "2_2") (pintype "passive"))
      (node (ref "C15") (pin "1") (pinfunction "1_1") (pintype "passive"))
      (node (ref "C16") (pin "1") (pinfunction "1_1") (pintype "passive"))
      (node (ref "C17") (pin "1") (pinfunction "1_1") (pintype "passive"))
      (node (ref "C18") (pin "1") (pinfunction "1_1") (pintype "passive"))
      (node (ref "C2") (pin "1") (pinfunction "1_1") (pintype "passive"))
      (node (ref "C25") (pin "1") (pinfunction "1_1") (pintype "passive"))
      (node (ref "C26") (pin "2") (pinfunction "2_2") (pintype "passive"))
      (node (ref "C27") (pin "1") (pinfunction "1_1") (pintype "passive"))
      (node (ref "C28") (pin "1") (pinfunction "1_1") (pintype "passive"))
      (node (ref "C29") (pin "1") (pinfunction "1_1") (pintype "passive"))
      (node (ref "C3") (pin "1") (pinfunction "1_1") (pintype "passive"))
      (node (ref "C30") (pin "1") (pinfunction "1_1") (pintype "passive"))
      (node (ref "C31") (pin "1") (pinfunction "1_1") (pintype "passive"))
      (node (ref "C32") (pin "1") (pinfunction "1_1") (pintype "passive"))
      (node (ref "C33") (pin "2") (pinfunction "2_2") (pintype "passive"))
      (node (ref "C34") (pin "1") (pinfunction "1_1") (pintype "passive"))
      (node (ref "C35") (pin "1") (pinfunction "1_1") (pintype "passive"))
      (node (ref "C36") (pin "1") (pinfunction "1_1") (pintype "passive"))
      (node (ref "C37") (pin "1") (pinfunction "1_1") (pintype "passive"))
      (node (ref "C38") (pin "1") (pinfunction "1_1") (pintype "passive"))
      (node (ref "C39") (pin "2") (pinfunction "2_2") (pintype "passive"))
      (node (ref "C4") (pin "2") (pinfunction "2_2") (pintype "passive"))
      (node (ref "C41") (pin "1") (pinfunction "1_1") (pintype "passive"))
      (node (ref "C42") (pin "1") (pinfunction "1_1") (pintype "passive"))
      (node (ref "C43") (pin "1") (pinfunction "1_1") (pintype "passive"))
      (node (ref "C44") (pin "1") (pinfunction "1_1") (pintype "passive"))
      (node (ref "C45") (pin "1") (pinfunction "1_1") (pintype "passive"))
      (node (ref "C46") (pin "1") (pinfunction "1_1") (pintype "passive"))
      (node (ref "C47") (pin "2") (pinfunction "2_2") (pintype "passive"))
      (node (ref "C48") (pin "1") (pinfunction "1_1") (pintype "passive"))
      (node (ref "C49") (pin "1") (pinfunction "1_1") (pintype "passive"))
      (node (ref "C5") (pin "2") (pinfunction "2_2") (pintype "passive"))
      (node (ref "C50") (pin "1") (pinfunction "1_1") (pintype "passive"))
      (node (ref "C51") (pin "1") (pinfunction "1_1") (pintype "passive"))
      (node (ref "C52") (pin "1") (pinfunction "1_1") (pintype "passive"))
      (node (ref "C53") (pin "2") (pinfunction "2_2") (pintype "passive"))
      (node (ref "C54") (pin "1") (pinfunction "1_1") (pintype "passive"))
      (node (ref "C55") (pin "1") (pinfunction "1_1") (pintype "passive"))
      (node (ref "C56") (pin "1") (pinfunction "1_1") (pintype "passive"))
      (node (ref "C57") (pin "1") (pinfunction "1_1") (pintype "passive"))
      (node (ref "C58") (pin "1") (pinfunction "1_1") (pintype "passive"))
      (node (ref "C59") (pin "1") (pinfunction "1_1") (pintype "passive"))
      (node (ref "C6") (pin "1") (pinfunction "1_1") (pintype "passive"))
      (node (ref "C60") (pin "2") (pinfunction "2_2") (pintype "passive"))
      (node (ref "C61") (pin "1") (pinfunction "1_1") (pintype "passive"))
      (node (ref "C62") (pin "1") (pinfunction "1_1") (pintype "passive"))
      (node (ref "C63") (pin "1") (pinfunction "1_1") (pintype "passive"))
      (node (ref "C64") (pin "1") (pinfunction "1_1") (pintype "passive"))
      (node (ref "C65") (pin "1") (pinfunction "1_1") (pintype "passive"))
      (node (ref "C66") (pin "2") (pinfunction "2_2") (pintype "passive"))
      (node (ref "C67") (pin "1") (pinfunction "1_1") (pintype "passive"))
      (node (ref "C68") (pin "1") (pinfunction "1_1") (pintype "passive"))
      (node (ref "C69") (pin "1") (pinfunction "1_1") (pintype "passive"))
      (node (ref "C7") (pin "1") (pinfunction "1_1") (pintype "passive"))
      (node (ref "C70") (pin "1") (pinfunction "1_1") (pintype "passive"))
      (node (ref "C71") (pin "1") (pinfunction "1_1") (pintype "passive"))
      (node (ref "C72") (pin "1") (pinfunction "1_1") (pintype "passive"))
      (node (ref "C73") (pin "2") (pinfunction "2_2") (pintype "passive"))
      (node (ref "C74") (pin "1") (pinfunction "1_1") (pintype "passive"))
      (node (ref "C75") (pin "1") (pinfunction "1_1") (pintype "passive"))
      (node (ref "C76") (pin "1") (pinfunction "1_1") (pintype "passive"))
      (node (ref "C77") (pin "1") (pinfunction "1_1") (pintype "passive"))
      (node (ref "C78") (pin "1") (pinfunction "1_1") (pintype "passive"))
      (node (ref "C79") (pin "2") (pinfunction "2_2") (pintype "passive"))
      (node (ref "C8") (pin "1") (pinfunction "1_1") (pintype "passive"))
      (node (ref "C80") (pin "1") (pinfunction "1_1") (pintype "passive"))
      (node (ref "C81") (pin "1") (pinfunction "1_1") (pintype "passive"))
      (node (ref "C82") (pin "1") (pinfunction "1_1") (pintype "passive"))
      (node (ref "C83") (pin "1") (pinfunction "1_1") (pintype "passive"))
      (node (ref "C84") (pin "1") (pinfunction "1_1") (pintype "passive"))
      (node (ref "C85") (pin "1") (pinfunction "1_1") (pintype "passive"))
      (node (ref "C86") (pin "2") (pinfunction "2_2") (pintype "passive"))
      (node (ref "C87") (pin "1") (pinfunction "1_1") (pintype "passive"))
      (node (ref "C88") (pin "1") (pinfunction "1_1") (pintype "passive"))
      (node (ref "C89") (pin "1") (pinfunction "1_1") (pintype "passive"))
      (node (ref "C9") (pin "2") (pinfunction "2_2") (pintype "passive"))
      (node (ref "C90") (pin "1") (pinfunction "1_1") (pintype "passive"))
      (node (ref "C91") (pin "1") (pinfunction "1_1") (pintype "passive"))
      (node (ref "C92") (pin "2") (pinfunction "2_2") (pintype "passive"))
      (node (ref "C93") (pin "1") (pinfunction "1_1") (pintype "passive"))
      (node (ref "IC1") (pin "7") (pinfunction "VEE_7") (pintype "power_in"))
      (node (ref "IC1") (pin "8") (pinfunction "GND_8") (pintype "power_in"))
      (node (ref "IC11") (pin "7") (pinfunction "VEE_7") (pintype "power_in"))
      (node (ref "IC11") (pin "8") (pinfunction "GND_8") (pintype "power_in"))
      (node (ref "IC14") (pin "7") (pinfunction "VEE_7") (pintype "power_in"))
      (node (ref "IC14") (pin "8") (pinfunction "GND_8") (pintype "power_in"))
      (node (ref "IC17") (pin "7") (pinfunction "VEE_7") (pintype "power_in"))
      (node (ref "IC17") (pin "8") (pinfunction "GND_8") (pintype "power_in"))
      (node (ref "IC2") (pin "14") (pinfunction "RSTSEL_14") (pintype "bidirectional"))
      (node (ref "IC2") (pin "15") (pinfunction "~{ENABLE}_15") (pintype "bidirectional"))
      (node (ref "IC2") (pin "5") (pinfunction "VREF_L_5") (pintype "bidirectional"))
      (node (ref "IC2") (pin "6") (pinfunction "GND_6") (pintype "bidirectional"))
      (node (ref "IC20") (pin "7") (pinfunction "VEE_7") (pintype "power_in"))
      (node (ref "IC20") (pin "8") (pinfunction "GND_8") (pintype "power_in"))
      (node (ref "IC26") (pin "7") (pinfunction "VEE_7") (pintype "power_in"))
      (node (ref "IC26") (pin "8") (pinfunction "GND_8") (pintype "power_in"))
      (node (ref "IC5") (pin "2") (pinfunction "GND_2") (pintype "passive"))
      (node (ref "IC5") (pin "2@1") (pinfunction "GND_2@1") (pintype "passive"))
      (node (ref "IC7") (pin "7") (pinfunction "VEE_7") (pintype "power_in"))
      (node (ref "IC7") (pin "8") (pinfunction "GND_8") (pintype "power_in"))
      (node (ref "R2") (pin "1") (pinfunction "1_1") (pintype "passive"))
      (node (ref "R3") (pin "1") (pinfunction "1_1") (pintype "passive"))
      (node (ref "R5") (pin "1") (pinfunction "1_1") (pintype "passive"))
      (node (ref "R7") (pin "1") (pinfunction "1_1") (pintype "passive"))
      (node (ref "X6") (pin "14") (pinfunction "14_14") (pintype "passive"))
    )
    (net (code "10") (name "DAC_1") (class "Default")
      (node (ref "IC26") (pin "3") (pinfunction "X_3") (pintype "bidirectional"))
      (node (ref "R9") (pin "2") (pinfunction "2_2") (pintype "passive"))
    )
    (net (code "11") (name "DAC_2") (class "Default")
      (node (ref "IC17") (pin "3") (pinfunction "X_3") (pintype "bidirectional"))
      (node (ref "IC20") (pin "3") (pinfunction "X_3") (pintype "bidirectional"))
      (node (ref "R10") (pin "2") (pinfunction "2_2") (pintype "passive"))
    )
    (net (code "12") (name "DAC_3") (class "Default")
      (node (ref "IC14") (pin "3") (pinfunction "X_3") (pintype "bidirectional"))
      (node (ref "IC7") (pin "3") (pinfunction "X_3") (pintype "bidirectional"))
      (node (ref "R11") (pin "2") (pinfunction "2_2") (pintype "passive"))
    )
    (net (code "13") (name "DAC_4") (class "Default")
      (node (ref "IC1") (pin "3") (pinfunction "X_3") (pintype "bidirectional"))
      (node (ref "IC11") (pin "3") (pinfunction "X_3") (pintype "bidirectional"))
      (node (ref "R12") (pin "2") (pinfunction "2_2") (pintype "passive"))
    )
    (net (code "14") (name "DAC_RAW_1") (class "Default")
      (node (ref "IC2") (pin "1") (pinfunction "OUT_A_1") (pintype "bidirectional"))
      (node (ref "IC8") (pin "3") (pinfunction "+IN_3") (pintype "input"))
    )
    (net (code "15") (name "DAC_RAW_2") (class "Default")
      (node (ref "IC2") (pin "2") (pinfunction "OUT_B_2") (pintype "bidirectional"))
      (node (ref "IC8") (pin "5") (pinfunction "+IN_5") (pintype "input"))
    )
    (net (code "16") (name "DAC_RAW_3") (class "Default")
      (node (ref "IC2") (pin "7") (pinfunction "OUT_C_7") (pintype "bidirectional"))
      (node (ref "IC8") (pin "10") (pinfunction "+IN_10") (pintype "input"))
    )
    (net (code "17") (name "DAC_RAW_4") (class "Default")
      (node (ref "IC2") (pin "8") (pinfunction "OUT_D_8") (pintype "bidirectional"))
      (node (ref "IC8") (pin "12") (pinfunction "+IN_12") (pintype "input"))
    )
    (net (code "18") (name "INH_0") (class "Default")
      (node (ref "IC1") (pin "6") (pinfunction "INH_6") (pintype "input"))
      (node (ref "IC20") (pin "6") (pinfunction "INH_6") (pintype "input"))
      (node (ref "IC26") (pin "6") (pinfunction "INH_6") (pintype "input"))
      (node (ref "IC7") (pin "6") (pinfunction "INH_6") (pintype "input"))
      (node (ref "X6") (pin "3") (pinfunction "3_3") (pintype "passive"))
    )
    (net (code "19") (name "INH_1") (class "Default")
      (node (ref "IC11") (pin "6") (pinfunction "INH_6") (pintype "input"))
      (node (ref "IC14") (pin "6") (pinfunction "INH_6") (pintype "input"))
      (node (ref "IC17") (pin "6") (pinfunction "INH_6") (pintype "input"))
      (node (ref "X6") (pin "6") (pinfunction "6_6") (pintype "passive"))
    )
    (net (code "20") (name "IN_0") (class "Default")
      (node (ref "C13") (pin "2") (pinfunction "2_2") (pintype "passive"))
      (node (ref "IC1") (pin "13") (pinfunction "X0_13") (pintype "bidirectional"))
      (node (ref "IC3") (pin "12") (pinfunction "+IN_12") (pintype "input"))
    )
    (net (code "21") (name "IN_1") (class "Default")
      (node (ref "C12") (pin "2") (pinfunction "2_2") (pintype "passive"))
      (node (ref "IC1") (pin "14") (pinfunction "X1_14") (pintype "bidirectional"))
      (node (ref "IC3") (pin "10") (pinfunction "+IN_10") (pintype "input"))
    )
    (net (code "22") (name "IN_2") (class "Default")
      (node (ref "C11") (pin "2") (pinfunction "2_2") (pintype "passive"))
      (node (ref "IC1") (pin "15") (pinfunction "X2_15") (pintype "bidirectional"))
      (node (ref "IC3") (pin "5") (pinfunction "+IN_5") (pintype "input"))
    )
    (net (code "23") (name "IN_3") (class "Default")
      (node (ref "C7") (pin "2") (pinfunction "2_2") (pintype "passive"))
      (node (ref "IC1") (pin "12") (pinfunction "X3_12") (pintype "bidirectional"))
      (node (ref "IC3") (pin "3") (pinfunction "+IN_3") (pintype "input"))
    )
    (net (code "24") (name "IN_4") (class "Default")
      (node (ref "C25") (pin "2") (pinfunction "2_2") (pintype "passive"))
      (node (ref "IC1") (pin "1") (pinfunction "X4_1") (pintype "bidirectional"))
      (node (ref "IC6") (pin "12") (pinfunction "+IN_12") (pintype "input"))
    )
    (net (code "25") (name "IN_5") (class "Default")
      (node (ref "C18") (pin "2") (pinfunction "2_2") (pintype "passive"))
      (node (ref "IC1") (pin "5") (pinfunction "X5_5") (pintype "bidirectional"))
      (node (ref "IC6") (pin "10") (pinfunction "+IN_10") (pintype "input"))
    )
    (net (code "26") (name "IN_6") (class "Default")
      (node (ref "C17") (pin "2") (pinfunction "2_2") (pintype "passive"))
      (node (ref "IC1") (pin "2") (pinfunction "X6_2") (pintype "bidirectional"))
      (node (ref "IC6") (pin "5") (pinfunction "+IN_5") (pintype "input"))
    )
    (net (code "27") (name "IN_7") (class "Default")
      (node (ref "C16") (pin "2") (pinfunction "2_2") (pintype "passive"))
      (node (ref "IC1") (pin "4") (pinfunction "X7_4") (pintype "bidirectional"))
      (node (ref "IC6") (pin "3") (pinfunction "+IN_3") (pintype "input"))
    )
    (net (code "28") (name "IN_8") (class "Default")
      (node (ref "C46") (pin "2") (pinfunction "2_2") (pintype "passive"))
      (node (ref "IC11") (pin "13") (pinfunction "X0_13") (pintype "bidirectional"))
      (node (ref "IC12") (pin "12") (pinfunction "+IN_12") (pintype "input"))
    )
    (net (code "29") (name "IN_9") (class "Default")
      (node (ref "C45") (pin "2") (pinfunction "2_2") (pintype "passive"))
      (node (ref "IC11") (pin "14") (pinfunction "X1_14") (pintype "bidirectional"))
      (node (ref "IC12") (pin "10") (pinfunction "+IN_10") (pintype "input"))
    )
    (net (code "30") (name "IN_10") (class "Default")
      (node (ref "C44") (pin "2") (pinfunction "2_2") (pintype "passive"))
      (node (ref "IC11") (pin "15") (pinfunction "X2_15") (pintype "bidirectional"))
      (node (ref "IC12") (pin "5") (pinfunction "+IN_5") (pintype "input"))
    )
    (net (code "31") (name "IN_11") (class "Default")
      (node (ref "C43") (pin "2") (pinfunction "2_2") (pintype "passive"))
      (node (ref "IC11") (pin "12") (pinfunction "X3_12") (pintype "bidirectional"))
      (node (ref "IC12") (pin "3") (pinfunction "+IN_3") (pintype "input"))
    )
    (net (code "32") (name "IN_12") (class "Default")
      (node (ref "C52") (pin "2") (pinfunction "2_2") (pintype "passive"))
      (node (ref "IC11") (pin "1") (pinfunction "X4_1") (pintype "bidirectional"))
      (node (ref "IC13") (pin "12") (pinfunction "+IN_12") (pintype "input"))
    )
    (net (code "33") (name "IN_13") (class "Default")
      (node (ref "C51") (pin "2") (pinfunction "2_2") (pintype "passive"))
      (node (ref "IC11") (pin "5") (pinfunction "X5_5") (pintype "bidirectional"))
      (node (ref "IC13") (pin "10") (pinfunction "+IN_10") (pintype "input"))
    )
    (net (code "34") (name "IN_14") (class "Default")
      (node (ref "C50") (pin "2") (pinfunction "2_2") (pintype "passive"))
      (node (ref "IC11") (pin "2") (pinfunction "X6_2") (pintype "bidirectional"))
      (node (ref "IC13") (pin "5") (pinfunction "+IN_5") (pintype "input"))
    )
    (net (code "35") (name "IN_15") (class "Default")
      (node (ref "C49") (pin "2") (pinfunction "2_2") (pintype "passive"))
      (node (ref "IC11") (pin "4") (pinfunction "X7_4") (pintype "bidirectional"))
      (node (ref "IC13") (pin "3") (pinfunction "+IN_3") (pintype "input"))
    )
    (net (code "36") (name "IN_16") (class "Default")
      (node (ref "C32") (pin "2") (pinfunction "2_2") (pintype "passive"))
      (node (ref "IC7") (pin "13") (pinfunction "X0_13") (pintype "bidirectional"))
      (node (ref "IC9") (pin "12") (pinfunction "+IN_12") (pintype "input"))
    )
    (net (code "37") (name "IN_17") (class "Default")
      (node (ref "C31") (pin "2") (pinfunction "2_2") (pintype "passive"))
      (node (ref "IC7") (pin "14") (pinfunction "X1_14") (pintype "bidirectional"))
      (node (ref "IC9") (pin "10") (pinfunction "+IN_10") (pintype "input"))
    )
    (net (code "38") (name "IN_18") (class "Default")
      (node (ref "C30") (pin "2") (pinfunction "2_2") (pintype "passive"))
      (node (ref "IC7") (pin "15") (pinfunction "X2_15") (pintype "bidirectional"))
      (node (ref "IC9") (pin "5") (pinfunction "+IN_5") (pintype "input"))
    )
    (net (code "39") (name "IN_19") (class "Default")
      (node (ref "C29") (pin "2") (pinfunction "2_2") (pintype "passive"))
      (node (ref "IC7") (pin "12") (pinfunction "X3_12") (pintype "bidirectional"))
      (node (ref "IC9") (pin "3") (pinfunction "+IN_3") (pintype "input"))
    )
    (net (code "40") (name "IN_20") (class "Default")
      (node (ref "C38") (pin "2") (pinfunction "2_2") (pintype "passive"))
      (node (ref "IC10") (pin "12") (pinfunction "+IN_12") (pintype "input"))
      (node (ref "IC7") (pin "1") (pinfunction "X4_1") (pintype "bidirectional"))
    )
    (net (code "41") (name "IN_21") (class "Default")
      (node (ref "C37") (pin "2") (pinfunction "2_2") (pintype "passive"))
      (node (ref "IC10") (pin "10") (pinfunction "+IN_10") (pintype "input"))
      (node (ref "IC7") (pin "5") (pinfunction "X5_5") (pintype "bidirectional"))
    )
    (net (code "42") (name "IN_22") (class "Default")
      (node (ref "C36") (pin "2") (pinfunction "2_2") (pintype "passive"))
      (node (ref "IC10") (pin "5") (pinfunction "+IN_5") (pintype "input"))
      (node (ref "IC7") (pin "2") (pinfunction "X6_2") (pintype "bidirectional"))
    )
    (net (code "43") (name "IN_23") (class "Default")
      (node (ref "C35") (pin "2") (pinfunction "2_2") (pintype "passive"))
      (node (ref "IC10") (pin "3") (pinfunction "+IN_3") (pintype "input"))
      (node (ref "IC7") (pin "4") (pinfunction "X7_4") (pintype "bidirectional"))
    )
    (net (code "44") (name "IN_24") (class "Default")
      (node (ref "C59") (pin "2") (pinfunction "2_2") (pintype "passive"))
      (node (ref "IC14") (pin "13") (pinfunction "X0_13") (pintype "bidirectional"))
      (node (ref "IC15") (pin "12") (pinfunction "+IN_12") (pintype "input"))
    )
    (net (code "45") (name "IN_25") (class "Default")
      (node (ref "C58") (pin "2") (pinfunction "2_2") (pintype "passive"))
      (node (ref "IC14") (pin "14") (pinfunction "X1_14") (pintype "bidirectional"))
      (node (ref "IC15") (pin "10") (pinfunction "+IN_10") (pintype "input"))
    )
    (net (code "46") (name "IN_26") (class "Default")
      (node (ref "C57") (pin "2") (pinfunction "2_2") (pintype "passive"))
      (node (ref "IC14") (pin "15") (pinfunction "X2_15") (pintype "bidirectional"))
      (node (ref "IC15") (pin "5") (pinfunction "+IN_5") (pintype "input"))
    )
    (net (code "47") (name "IN_27") (class "Default")
      (node (ref "C56") (pin "2") (pinfunction "2_2") (pintype "passive"))
      (node (ref "IC14") (pin "12") (pinfunction "X3_12") (pintype "bidirectional"))
      (node (ref "IC15") (pin "3") (pinfunction "+IN_3") (pintype "input"))
    )
    (net (code "48") (name "IN_28") (class "Default")
      (node (ref "C65") (pin "2") (pinfunction "2_2") (pintype "passive"))
      (node (ref "IC14") (pin "1") (pinfunction "X4_1") (pintype "bidirectional"))
      (node (ref "IC16") (pin "12") (pinfunction "+IN_12") (pintype "input"))
    )
    (net (code "49") (name "IN_29") (class "Default")
      (node (ref "C64") (pin "2") (pinfunction "2_2") (pintype "passive"))
      (node (ref "IC14") (pin "5") (pinfunction "X5_5") (pintype "bidirectional"))
      (node (ref "IC16") (pin "10") (pinfunction "+IN_10") (pintype "input"))
    )
    (net (code "50") (name "IN_30") (class "Default")
      (node (ref "C63") (pin "2") (pinfunction "2_2") (pintype "passive"))
      (node (ref "IC14") (pin "2") (pinfunction "X6_2") (pintype "bidirectional"))
      (node (ref "IC16") (pin "5") (pinfunction "+IN_5") (pintype "input"))
    )
    (net (code "51") (name "IN_31") (class "Default")
      (node (ref "C62") (pin "2") (pinfunction "2_2") (pintype "passive"))
      (node (ref "IC14") (pin "4") (pinfunction "X7_4") (pintype "bidirectional"))
      (node (ref "IC16") (pin "3") (pinfunction "+IN_3") (pintype "input"))
    )
    (net (code "52") (name "IN_32") (class "Default")
      (node (ref "C85") (pin "2") (pinfunction "2_2") (pintype "passive"))
      (node (ref "IC20") (pin "13") (pinfunction "X0_13") (pintype "bidirectional"))
      (node (ref "IC21") (pin "12") (pinfunction "+IN_12") (pintype "input"))
    )
    (net (code "53") (name "IN_33") (class "Default")
      (node (ref "C84") (pin "2") (pinfunction "2_2") (pintype "passive"))
      (node (ref "IC20") (pin "14") (pinfunction "X1_14") (pintype "bidirectional"))
      (node (ref "IC21") (pin "10") (pinfunction "+IN_10") (pintype "input"))
    )
    (net (code "54") (name "IN_34") (class "Default")
      (node (ref "C83") (pin "2") (pinfunction "2_2") (pintype "passive"))
      (node (ref "IC20") (pin "15") (pinfunction "X2_15") (pintype "bidirectional"))
      (node (ref "IC21") (pin "5") (pinfunction "+IN_5") (pintype "input"))
    )
    (net (code "55") (name "IN_35") (class "Default")
      (node (ref "C82") (pin "2") (pinfunction "2_2") (pintype "passive"))
      (node (ref "IC20") (pin "12") (pinfunction "X3_12") (pintype "bidirectional"))
      (node (ref "IC21") (pin "3") (pinfunction "+IN_3") (pintype "input"))
    )
    (net (code "56") (name "IN_36") (class "Default")
      (node (ref "C91") (pin "2") (pinfunction "2_2") (pintype "passive"))
      (node (ref "IC20") (pin "1") (pinfunction "X4_1") (pintype "bidirectional"))
      (node (ref "IC22") (pin "12") (pinfunction "+IN_12") (pintype "input"))
    )
    (net (code "57") (name "IN_37") (class "Default")
      (node (ref "C90") (pin "2") (pinfunction "2_2") (pintype "passive"))
      (node (ref "IC20") (pin "5") (pinfunction "X5_5") (pintype "bidirectional"))
      (node (ref "IC22") (pin "10") (pinfunction "+IN_10") (pintype "input"))
    )
    (net (code "58") (name "IN_38") (class "Default")
      (node (ref "C89") (pin "2") (pinfunction "2_2") (pintype "passive"))
      (node (ref "IC20") (pin "2") (pinfunction "X6_2") (pintype "bidirectional"))
      (node (ref "IC22") (pin "5") (pinfunction "+IN_5") (pintype "input"))
    )
    (net (code "59") (name "IN_39") (class "Default")
      (node (ref "C88") (pin "2") (pinfunction "2_2") (pintype "passive"))
      (node (ref "IC20") (pin "4") (pinfunction "X7_4") (pintype "bidirectional"))
      (node (ref "IC22") (pin "3") (pinfunction "+IN_3") (pintype "input"))
    )
    (net (code "60") (name "IN_40") (class "Default")
      (node (ref "C72") (pin "2") (pinfunction "2_2") (pintype "passive"))
      (node (ref "IC17") (pin "13") (pinfunction "X0_13") (pintype "bidirectional"))
      (node (ref "IC18") (pin "12") (pinfunction "+IN_12") (pintype "input"))
    )
    (net (code "61") (name "IN_41") (class "Default")
      (node (ref "C71") (pin "2") (pinfunction "2_2") (pintype "passive"))
      (node (ref "IC17") (pin "14") (pinfunction "X1_14") (pintype "bidirectional"))
      (node (ref "IC18") (pin "10") (pinfunction "+IN_10") (pintype "input"))
    )
    (net (code "62") (name "IN_42") (class "Default")
      (node (ref "C70") (pin "2") (pinfunction "2_2") (pintype "passive"))
      (node (ref "IC17") (pin "15") (pinfunction "X2_15") (pintype "bidirectional"))
      (node (ref "IC18") (pin "5") (pinfunction "+IN_5") (pintype "input"))
    )
    (net (code "63") (name "IN_43") (class "Default")
      (node (ref "C69") (pin "2") (pinfunction "2_2") (pintype "passive"))
      (node (ref "IC17") (pin "12") (pinfunction "X3_12") (pintype "bidirectional"))
      (node (ref "IC18") (pin "3") (pinfunction "+IN_3") (pintype "input"))
    )
    (net (code "64") (name "IN_44") (class "Default")
      (node (ref "C78") (pin "2") (pinfunction "2_2") (pintype "passive"))
      (node (ref "IC17") (pin "1") (pinfunction "X4_1") (pintype "bidirectional"))
      (node (ref "IC19") (pin "12") (pinfunction "+IN_12") (pintype "input"))
    )
    (net (code "65") (name "IN_45") (class "Default")
      (node (ref "C77") (pin "2") (pinfunction "2_2") (pintype "passive"))
      (node (ref "IC17") (pin "5") (pinfunction "X5_5") (pintype "bidirectional"))
      (node (ref "IC19") (pin "10") (pinfunction "+IN_10") (pintype "input"))
    )
    (net (code "66") (name "IN_46") (class "Default")
      (node (ref "C76") (pin "2") (pinfunction "2_2") (pintype "passive"))
      (node (ref "IC17") (pin "2") (pinfunction "X6_2") (pintype "bidirectional"))
      (node (ref "IC19") (pin "5") (pinfunction "+IN_5") (pintype "input"))
    )
    (net (code "67") (name "IN_47") (class "Default")
      (node (ref "C75") (pin "2") (pinfunction "2_2") (pintype "passive"))
      (node (ref "IC17") (pin "4") (pinfunction "X7_4") (pintype "bidirectional"))
      (node (ref "IC19") (pin "3") (pinfunction "+IN_3") (pintype "input"))
    )
    (net (code "68") (name "IN_48") (class "Default")
      (node (ref "C111") (pin "2") (pinfunction "2_2") (pintype "passive"))
      (node (ref "IC26") (pin "13") (pinfunction "X0_13") (pintype "bidirectional"))
      (node (ref "IC27") (pin "12") (pinfunction "+IN_12") (pintype "input"))
    )
    (net (code "69") (name "IN_49") (class "Default")
      (node (ref "C110") (pin "2") (pinfunction "2_2") (pintype "passive"))
      (node (ref "IC26") (pin "14") (pinfunction "X1_14") (pintype "bidirectional"))
      (node (ref "IC27") (pin "10") (pinfunction "+IN_10") (pintype "input"))
    )
    (net (code "70") (name "IN_50") (class "Default")
      (node (ref "C109") (pin "2") (pinfunction "2_2") (pintype "passive"))
      (node (ref "IC26") (pin "15") (pinfunction "X2_15") (pintype "bidirectional"))
      (node (ref "IC27") (pin "5") (pinfunction "+IN_5") (pintype "input"))
    )
    (net (code "71") (name "IN_51") (class "Default")
      (node (ref "C108") (pin "2") (pinfunction "2_2") (pintype "passive"))
      (node (ref "IC26") (pin "12") (pinfunction "X3_12") (pintype "bidirectional"))
      (node (ref "IC27") (pin "3") (pinfunction "+IN_3") (pintype "input"))
    )
    (net (code "72") (name "IN_52") (class "Default")
      (node (ref "C117") (pin "2") (pinfunction "2_2") (pintype "passive"))
      (node (ref "IC26") (pin "1") (pinfunction "X4_1") (pintype "bidirectional"))
      (node (ref "IC28") (pin "12") (pinfunction "+IN_12") (pintype "input"))
    )
    (net (code "73") (name "IN_53") (class "Default")
      (node (ref "C116") (pin "2") (pinfunction "2_2") (pintype "passive"))
      (node (ref "IC26") (pin "5") (pinfunction "X5_5") (pintype "bidirectional"))
      (node (ref "IC28") (pin "10") (pinfunction "+IN_10") (pintype "input"))
    )
    (net (code "74") (name "IN_54") (class "Default")
      (node (ref "C115") (pin "2") (pinfunction "2_2") (pintype "passive"))
      (node (ref "IC26") (pin "2") (pinfunction "X6_2") (pintype "bidirectional"))
      (node (ref "IC28") (pin "5") (pinfunction "+IN_5") (pintype "input"))
    )
    (net (code "75") (name "IN_55") (class "Default")
      (node (ref "C114") (pin "2") (pinfunction "2_2") (pintype "passive"))
      (node (ref "IC26") (pin "4") (pinfunction "X7_4") (pintype "bidirectional"))
      (node (ref "IC28") (pin "3") (pinfunction "+IN_3") (pintype "input"))
    )
    (net (code "76") (name "LDAC") (class "Default")
      (node (ref "IC2") (pin "16") (pinfunction "LDAC_16") (pintype "bidirectional"))
      (node (ref "X6") (pin "9") (pinfunction "9_9") (pintype "passive"))
    )
    (net (code "77") (name "Net-(IC2-IOVDD)") (class "Default")
      (node (ref "C9") (pin "1") (pinfunction "1_1") (pintype "passive"))
      (node (ref "IC2") (pin "12") (pinfunction "IOVDD_12") (pintype "power_in"))
      (node (ref "JP1") (pin "2") (pinfunction "2_2") (pintype "passive"))
    )
    (net (code "78") (name "Net-(IC8A--IN)") (class "Default")
      (node (ref "IC8") (pin "2") (pinfunction "-IN_2") (pintype "input"))
      (node (ref "R1") (pin "1") (pinfunction "1_1") (pintype "passive"))
      (node (ref "R2") (pin "2") (pinfunction "2_2") (pintype "passive"))
    )
    (net (code "79") (name "Net-(IC8A-OUT)") (class "Default")
      (node (ref "IC8") (pin "1") (pinfunction "OUT_1") (pintype "output"))
      (node (ref "R1") (pin "2") (pinfunction "2_2") (pintype "passive"))
      (node (ref "R9") (pin "1") (pinfunction "1_1") (pintype "passive"))
    )
    (net (code "80") (name "Net-(IC8B--IN)") (class "Default")
      (node (ref "IC8") (pin "6") (pinfunction "-IN_6") (pintype "input"))
      (node (ref "R3") (pin "2") (pinfunction "2_2") (pintype "passive"))
      (node (ref "R4") (pin "1") (pinfunction "1_1") (pintype "passive"))
    )
    (net (code "81") (name "Net-(IC8B-OUT)") (class "Default")
      (node (ref "IC8") (pin "7") (pinfunction "OUT_7") (pintype "output"))
      (node (ref "R10") (pin "1") (pinfunction "1_1") (pintype "passive"))
      (node (ref "R4") (pin "2") (pinfunction "2_2") (pintype "passive"))
    )
    (net (code "82") (name "Net-(IC8C--IN)") (class "Default")
      (node (ref "IC8") (pin "9") (pinfunction "-IN_9") (pintype "input"))
      (node (ref "R5") (pin "2") (pinfunction "2_2") (pintype "passive"))
      (node (ref "R6") (pin "1") (pinfunction "1_1") (pintype "passive"))
    )
    (net (code "83") (name "Net-(IC8C-OUT)") (class "Default")
      (node (ref "IC8") (pin "8") (pinfunction "OUT_8") (pintype "output"))
      (node (ref "R11") (pin "1") (pinfunction "1_1") (pintype "passive"))
      (node (ref "R6") (pin "2") (pinfunction "2_2") (pintype "passive"))
    )
    (net (code "84") (name "Net-(IC8D--IN)") (class "Default")
      (node (ref "IC8") (pin "13") (pinfunction "-IN_13") (pintype "input"))
      (node (ref "R7") (pin "2") (pinfunction "2_2") (pintype "passive"))
      (node (ref "R8") (pin "1") (pinfunction "1_1") (pintype "passive"))
    )
    (net (code "85") (name "Net-(IC8D-OUT)") (class "Default")
      (node (ref "IC8") (pin "14") (pinfunction "OUT_14") (pintype "output"))
      (node (ref "R12") (pin "1") (pinfunction "1_1") (pintype "passive"))
      (node (ref "R8") (pin "2") (pinfunction "2_2") (pintype "passive"))
    )
    (net (code "86") (name "OUT_0") (class "Default")
      (node (ref "IC3") (pin "13") (pinfunction "-IN_13") (pintype "input"))
      (node (ref "IC3") (pin "14") (pinfunction "OUT_14") (pintype "output"))
      (node (ref "U$2") (pin "1") (pinfunction "1_1") (pintype "passive"))
      (node (ref "U$2") (pin "2") (pinfunction "2_2") (pintype "passive"))
    )
    (net (code "87") (name "OUT_1") (class "Default")
      (node (ref "IC3") (pin "8") (pinfunction "OUT_8") (pintype "output"))
      (node (ref "IC3") (pin "9") (pinfunction "-IN_9") (pintype "input"))
      (node (ref "U$2") (pin "3") (pinfunction "3_3") (pintype "passive"))
      (node (ref "U$2") (pin "4") (pinfunction "4_4") (pintype "passive"))
    )
    (net (code "88") (name "OUT_2") (class "Default")
      (node (ref "IC3") (pin "6") (pinfunction "-IN_6") (pintype "input"))
      (node (ref "IC3") (pin "7") (pinfunction "OUT_7") (pintype "output"))
      (node (ref "U$2") (pin "5") (pinfunction "5_5") (pintype "passive"))
      (node (ref "U$2") (pin "6") (pinfunction "6_6") (pintype "passive"))
    )
    (net (code "89") (name "OUT_3") (class "Default")
      (node (ref "IC3") (pin "1") (pinfunction "OUT_1") (pintype "output"))
      (node (ref "IC3") (pin "2") (pinfunction "-IN_2") (pintype "input"))
      (node (ref "U$2") (pin "7") (pinfunction "7_7") (pintype "passive"))
      (node (ref "U$2") (pin "8") (pinfunction "8_8") (pintype "passive"))
    )
    (net (code "90") (name "OUT_4") (class "Default")
      (node (ref "IC6") (pin "13") (pinfunction "-IN_13") (pintype "input"))
      (node (ref "IC6") (pin "14") (pinfunction "OUT_14") (pintype "output"))
      (node (ref "U$2") (pin "10") (pinfunction "10_10") (pintype "passive"))
      (node (ref "U$2") (pin "9") (pinfunction "9_9") (pintype "passive"))
    )
    (net (code "91") (name "OUT_5") (class "Default")
      (node (ref "IC6") (pin "8") (pinfunction "OUT_8") (pintype "output"))
      (node (ref "IC6") (pin "9") (pinfunction "-IN_9") (pintype "input"))
      (node (ref "U$2") (pin "11") (pinfunction "11_11") (pintype "passive"))
      (node (ref "U$2") (pin "12") (pinfunction "12_12") (pintype "passive"))
    )
    (net (code "92") (name "OUT_6") (class "Default")
      (node (ref "IC6") (pin "6") (pinfunction "-IN_6") (pintype "input"))
      (node (ref "IC6") (pin "7") (pinfunction "OUT_7") (pintype "output"))
      (node (ref "U$2") (pin "13") (pinfunction "13_13") (pintype "passive"))
      (node (ref "U$2") (pin "14") (pinfunction "14_14") (pintype "passive"))
    )
    (net (code "93") (name "OUT_7") (class "Default")
      (node (ref "IC6") (pin "1") (pinfunction "OUT_1") (pintype "output"))
      (node (ref "IC6") (pin "2") (pinfunction "-IN_2") (pintype "input"))
      (node (ref "U$2") (pin "15") (pinfunction "15_15") (pintype "passive"))
      (node (ref "U$2") (pin "16") (pinfunction "16_16") (pintype "passive"))
    )
    (net (code "94") (name "OUT_8") (class "Default")
      (node (ref "IC12") (pin "13") (pinfunction "-IN_13") (pintype "input"))
      (node (ref "IC12") (pin "14") (pinfunction "OUT_14") (pintype "output"))
      (node (ref "U$2") (pin "17") (pinfunction "17_17") (pintype "passive"))
      (node (ref "U$2") (pin "18") (pinfunction "18_18") (pintype "passive"))
    )
    (net (code "95") (name "OUT_9") (class "Default")
      (node (ref "IC12") (pin "8") (pinfunction "OUT_8") (pintype "output"))
      (node (ref "IC12") (pin "9") (pinfunction "-IN_9") (pintype "input"))
      (node (ref "U$2") (pin "19") (pinfunction "19_19") (pintype "passive"))
      (node (ref "U$2") (pin "20") (pinfunction "20_20") (pintype "passive"))
    )
    (net (code "96") (name "OUT_10") (class "Default")
      (node (ref "IC12") (pin "6") (pinfunction "-IN_6") (pintype "input"))
      (node (ref "IC12") (pin "7") (pinfunction "OUT_7") (pintype "output"))
      (node (ref "U$2") (pin "21") (pinfunction "21_21") (pintype "passive"))
      (node (ref "U$2") (pin "22") (pinfunction "22_22") (pintype "passive"))
    )
    (net (code "97") (name "OUT_11") (class "Default")
      (node (ref "IC12") (pin "1") (pinfunction "OUT_1") (pintype "output"))
      (node (ref "IC12") (pin "2") (pinfunction "-IN_2") (pintype "input"))
      (node (ref "U$2") (pin "23") (pinfunction "23_23") (pintype "passive"))
      (node (ref "U$2") (pin "24") (pinfunction "24_24") (pintype "passive"))
    )
    (net (code "98") (name "OUT_12") (class "Default")
      (node (ref "IC13") (pin "13") (pinfunction "-IN_13") (pintype "input"))
      (node (ref "IC13") (pin "14") (pinfunction "OUT_14") (pintype "output"))
      (node (ref "U$2") (pin "25") (pinfunction "25_25") (pintype "passive"))
      (node (ref "U$2") (pin "26") (pinfunction "26_26") (pintype "passive"))
    )
    (net (code "99") (name "OUT_13") (class "Default")
      (node (ref "IC13") (pin "8") (pinfunction "OUT_8") (pintype "output"))
      (node (ref "IC13") (pin "9") (pinfunction "-IN_9") (pintype "input"))
      (node (ref "U$2") (pin "27") (pinfunction "27_27") (pintype "passive"))
      (node (ref "U$2") (pin "28") (pinfunction "28_28") (pintype "passive"))
    )
    (net (code "100") (name "OUT_14") (class "Default")
      (node (ref "IC13") (pin "6") (pinfunction "-IN_6") (pintype "input"))
      (node (ref "IC13") (pin "7") (pinfunction "OUT_7") (pintype "output"))
      (node (ref "U$2") (pin "29") (pinfunction "29_29") (pintype "passive"))
      (node (ref "U$2") (pin "30") (pinfunction "30_30") (pintype "passive"))
    )
    (net (code "101") (name "OUT_15") (class "Default")
      (node (ref "IC13") (pin "1") (pinfunction "OUT_1") (pintype "output"))
      (node (ref "IC13") (pin "2") (pinfunction "-IN_2") (pintype "input"))
      (node (ref "X5") (pin "1") (pinfunction "1_1") (pintype "passive"))
    )
    (net (code "102") (name "OUT_16") (class "Default")
      (node (ref "IC9") (pin "13") (pinfunction "-IN_13") (pintype "input"))
      (node (ref "IC9") (pin "14") (pinfunction "OUT_14") (pintype "output"))
      (node (ref "U$3") (pin "1") (pinfunction "1_1") (pintype "passive"))
      (node (ref "U$3") (pin "2") (pinfunction "2_2") (pintype "passive"))
    )
    (net (code "103") (name "OUT_17") (class "Default")
      (node (ref "IC9") (pin "8") (pinfunction "OUT_8") (pintype "output"))
      (node (ref "IC9") (pin "9") (pinfunction "-IN_9") (pintype "input"))
      (node (ref "U$3") (pin "3") (pinfunction "3_3") (pintype "passive"))
      (node (ref "U$3") (pin "4") (pinfunction "4_4") (pintype "passive"))
    )
    (net (code "104") (name "OUT_18") (class "Default")
      (node (ref "IC9") (pin "6") (pinfunction "-IN_6") (pintype "input"))
      (node (ref "IC9") (pin "7") (pinfunction "OUT_7") (pintype "output"))
      (node (ref "U$3") (pin "5") (pinfunction "5_5") (pintype "passive"))
      (node (ref "U$3") (pin "6") (pinfunction "6_6") (pintype "passive"))
    )
    (net (code "105") (name "OUT_19") (class "Default")
      (node (ref "IC9") (pin "1") (pinfunction "OUT_1") (pintype "output"))
      (node (ref "IC9") (pin "2") (pinfunction "-IN_2") (pintype "input"))
      (node (ref "U$3") (pin "7") (pinfunction "7_7") (pintype "passive"))
      (node (ref "U$3") (pin "8") (pinfunction "8_8") (pintype "passive"))
    )
    (net (code "106") (name "OUT_20") (class "Default")
      (node (ref "IC10") (pin "13") (pinfunction "-IN_13") (pintype "input"))
      (node (ref "IC10") (pin "14") (pinfunction "OUT_14") (pintype "output"))
      (node (ref "U$3") (pin "10") (pinfunction "10_10") (pintype "passive"))
      (node (ref "U$3") (pin "9") (pinfunction "9_9") (pintype "passive"))
    )
    (net (code "107") (name "OUT_21") (class "Default")
      (node (ref "IC10") (pin "8") (pinfunction "OUT_8") (pintype "output"))
      (node (ref "IC10") (pin "9") (pinfunction "-IN_9") (pintype "input"))
      (node (ref "U$3") (pin "11") (pinfunction "11_11") (pintype "passive"))
      (node (ref "U$3") (pin "12") (pinfunction "12_12") (pintype "passive"))
    )
    (net (code "108") (name "OUT_22") (class "Default")
      (node (ref "IC10") (pin "6") (pinfunction "-IN_6") (pintype "input"))
      (node (ref "IC10") (pin "7") (pinfunction "OUT_7") (pintype "output"))
      (node (ref "U$3") (pin "13") (pinfunction "13_13") (pintype "passive"))
      (node (ref "U$3") (pin "14") (pinfunction "14_14") (pintype "passive"))
    )
    (net (code "109") (name "OUT_23") (class "Default")
      (node (ref "IC10") (pin "1") (pinfunction "OUT_1") (pintype "output"))
      (node (ref "IC10") (pin "2") (pinfunction "-IN_2") (pintype "input"))
      (node (ref "U$3") (pin "15") (pinfunction "15_15") (pintype "passive"))
      (node (ref "U$3") (pin "16") (pinfunction "16_16") (pintype "passive"))
    )
    (net (code "110") (name "OUT_24") (class "Default")
      (node (ref "IC15") (pin "13") (pinfunction "-IN_13") (pintype "input"))
      (node (ref "IC15") (pin "14") (pinfunction "OUT_14") (pintype "output"))
      (node (ref "U$3") (pin "17") (pinfunction "17_17") (pintype "passive"))
      (node (ref "U$3") (pin "18") (pinfunction "18_18") (pintype "passive"))
    )
    (net (code "111") (name "OUT_25") (class "Default")
      (node (ref "IC15") (pin "8") (pinfunction "OUT_8") (pintype "output"))
      (node (ref "IC15") (pin "9") (pinfunction "-IN_9") (pintype "input"))
      (node (ref "U$3") (pin "19") (pinfunction "19_19") (pintype "passive"))
      (node (ref "U$3") (pin "20") (pinfunction "20_20") (pintype "passive"))
    )
    (net (code "112") (name "OUT_26") (class "Default")
      (node (ref "IC15") (pin "6") (pinfunction "-IN_6") (pintype "input"))
      (node (ref "IC15") (pin "7") (pinfunction "OUT_7") (pintype "output"))
      (node (ref "U$3") (pin "21") (pinfunction "21_21") (pintype "passive"))
      (node (ref "U$3") (pin "22") (pinfunction "22_22") (pintype "passive"))
    )
    (net (code "113") (name "OUT_27") (class "Default")
      (node (ref "IC15") (pin "1") (pinfunction "OUT_1") (pintype "output"))
      (node (ref "IC15") (pin "2") (pinfunction "-IN_2") (pintype "input"))
      (node (ref "U$3") (pin "23") (pinfunction "23_23") (pintype "passive"))
      (node (ref "U$3") (pin "24") (pinfunction "24_24") (pintype "passive"))
    )
    (net (code "114") (name "OUT_28") (class "Default")
      (node (ref "IC16") (pin "13") (pinfunction "-IN_13") (pintype "input"))
      (node (ref "IC16") (pin "14") (pinfunction "OUT_14") (pintype "output"))
      (node (ref "U$3") (pin "25") (pinfunction "25_25") (pintype "passive"))
      (node (ref "U$3") (pin "26") (pinfunction "26_26") (pintype "passive"))
    )
    (net (code "115") (name "OUT_29") (class "Default")
      (node (ref "IC16") (pin "8") (pinfunction "OUT_8") (pintype "output"))
      (node (ref "IC16") (pin "9") (pinfunction "-IN_9") (pintype "input"))
      (node (ref "U$3") (pin "27") (pinfunction "27_27") (pintype "passive"))
      (node (ref "U$3") (pin "28") (pinfunction "28_28") (pintype "passive"))
    )
    (net (code "116") (name "OUT_30") (class "Default")
      (node (ref "IC16") (pin "6") (pinfunction "-IN_6") (pintype "input"))
      (node (ref "IC16") (pin "7") (pinfunction "OUT_7") (pintype "output"))
      (node (ref "U$3") (pin "29") (pinfunction "29_29") (pintype "passive"))
      (node (ref "U$3") (pin "30") (pinfunction "30_30") (pintype "passive"))
    )
    (net (code "117") (name "OUT_31") (class "Default")
      (node (ref "IC16") (pin "1") (pinfunction "OUT_1") (pintype "output"))
      (node (ref "IC16") (pin "2") (pinfunction "-IN_2") (pintype "input"))
      (node (ref "X9") (pin "1") (pinfunction "1_1") (pintype "passive"))
    )
    (net (code "118") (name "OUT_32") (class "Default")
      (node (ref "IC21") (pin "13") (pinfunction "-IN_13") (pintype "input"))
      (node (ref "IC21") (pin "14") (pinfunction "OUT_14") (pintype "output"))
      (node (ref "X9") (pin "2") (pinfunction "2_2") (pintype "passive"))
    )
    (net (code "119") (name "OUT_33") (class "Default")
      (node (ref "IC21") (pin "8") (pinfunction "OUT_8") (pintype "output"))
      (node (ref "IC21") (pin "9") (pinfunction "-IN_9") (pintype "input"))
      (node (ref "X10") (pin "1") (pinfunction "1_1") (pintype "passive"))
      (node (ref "X10") (pin "2") (pinfunction "2_2") (pintype "passive"))
    )
    (net (code "120") (name "OUT_34") (class "Default")
      (node (ref "IC21") (pin "6") (pinfunction "-IN_6") (pintype "input"))
      (node (ref "IC21") (pin "7") (pinfunction "OUT_7") (pintype "output"))
      (node (ref "X10") (pin "3") (pinfunction "3_3") (pintype "passive"))
      (node (ref "X10") (pin "4") (pinfunction "4_4") (pintype "passive"))
    )
    (net (code "121") (name "OUT_35") (class "Default")
      (node (ref "IC21") (pin "1") (pinfunction "OUT_1") (pintype "output"))
      (node (ref "IC21") (pin "2") (pinfunction "-IN_2") (pintype "input"))
      (node (ref "X10") (pin "5") (pinfunction "5_5") (pintype "passive"))
      (node (ref "X10") (pin "6") (pinfunction "6_6") (pintype "passive"))
    )
    (net (code "122") (name "OUT_36") (class "Default")
      (node (ref "IC22") (pin "13") (pinfunction "-IN_13") (pintype "input"))
      (node (ref "IC22") (pin "14") (pinfunction "OUT_14") (pintype "output"))
      (node (ref "X10") (pin "7") (pinfunction "7_7") (pintype "passive"))
      (node (ref "X10") (pin "8") (pinfunction "8_8") (pintype "passive"))
    )
    (net (code "123") (name "OUT_37") (class "Default")
      (node (ref "IC22") (pin "8") (pinfunction "OUT_8") (pintype "output"))
      (node (ref "IC22") (pin "9") (pinfunction "-IN_9") (pintype "input"))
      (node (ref "X10") (pin "10") (pinfunction "10_10") (pintype "passive"))
      (node (ref "X10") (pin "9") (pinfunction "9_9") (pintype "passive"))
    )
    (net (code "124") (name "OUT_38") (class "Default")
      (node (ref "IC22") (pin "6") (pinfunction "-IN_6") (pintype "input"))
      (node (ref "IC22") (pin "7") (pinfunction "OUT_7") (pintype "output"))
      (node (ref "X10") (pin "11") (pinfunction "11_11") (pintype "passive"))
      (node (ref "X10") (pin "12") (pinfunction "12_12") (pintype "passive"))
    )
    (net (code "125") (name "OUT_39") (class "Default")
      (node (ref "IC22") (pin "1") (pinfunction "OUT_1") (pintype "output"))
      (node (ref "IC22") (pin "2") (pinfunction "-IN_2") (pintype "input"))
      (node (ref "X10") (pin "13") (pinfunction "13_13") (pintype "passive"))
      (node (ref "X10") (pin "14") (pinfunction "14_14") (pintype "passive"))
    )
    (net (code "126") (name "OUT_40") (class "Default")
      (node (ref "IC18") (pin "13") (pinfunction "-IN_13") (pintype "input"))
      (node (ref "IC18") (pin "14") (pinfunction "OUT_14") (pintype "output"))
      (node (ref "X4") (pin "1") (pinfunction "1_1") (pintype "passive"))
    )
    (net (code "127") (name "OUT_41") (class "Default")
      (node (ref "IC18") (pin "8") (pinfunction "OUT_8") (pintype "output"))
      (node (ref "IC18") (pin "9") (pinfunction "-IN_9") (pintype "input"))
      (node (ref "U$4") (pin "1") (pinfunction "1_1") (pintype "passive"))
      (node (ref "U$4") (pin "2") (pinfunction "2_2") (pintype "passive"))
    )
    (net (code "128") (name "OUT_42") (class "Default")
      (node (ref "IC18") (pin "6") (pinfunction "-IN_6") (pintype "input"))
      (node (ref "IC18") (pin "7") (pinfunction "OUT_7") (pintype "output"))
      (node (ref "U$4") (pin "3") (pinfunction "3_3") (pintype "passive"))
      (node (ref "U$4") (pin "4") (pinfunction "4_4") (pintype "passive"))
    )
    (net (code "129") (name "OUT_43") (class "Default")
      (node (ref "IC18") (pin "1") (pinfunction "OUT_1") (pintype "output"))
      (node (ref "IC18") (pin "2") (pinfunction "-IN_2") (pintype "input"))
      (node (ref "U$4") (pin "5") (pinfunction "5_5") (pintype "passive"))
      (node (ref "U$4") (pin "6") (pinfunction "6_6") (pintype "passive"))
    )
    (net (code "130") (name "OUT_44") (class "Default")
      (node (ref "IC19") (pin "13") (pinfunction "-IN_13") (pintype "input"))
      (node (ref "IC19") (pin "14") (pinfunction "OUT_14") (pintype "output"))
      (node (ref "U$4") (pin "7") (pinfunction "7_7") (pintype "passive"))
      (node (ref "U$4") (pin "8") (pinfunction "8_8") (pintype "passive"))
    )
    (net (code "131") (name "OUT_45") (class "Default")
      (node (ref "IC19") (pin "8") (pinfunction "OUT_8") (pintype "output"))
      (node (ref "IC19") (pin "9") (pinfunction "-IN_9") (pintype "input"))
      (node (ref "U$4") (pin "10") (pinfunction "10_10") (pintype "passive"))
      (node (ref "U$4") (pin "9") (pinfunction "9_9") (pintype "passive"))
    )
    (net (code "132") (name "OUT_46") (class "Default")
      (node (ref "IC19") (pin "6") (pinfunction "-IN_6") (pintype "input"))
      (node (ref "IC19") (pin "7") (pinfunction "OUT_7") (pintype "output"))
      (node (ref "U$4") (pin "11") (pinfunction "11_11") (pintype "passive"))
      (node (ref "U$4") (pin "12") (pinfunction "12_12") (pintype "passive"))
    )
    (net (code "133") (name "OUT_47") (class "Default")
      (node (ref "IC19") (pin "1") (pinfunction "OUT_1") (pintype "output"))
      (node (ref "IC19") (pin "2") (pinfunction "-IN_2") (pintype "input"))
      (node (ref "U$4") (pin "13") (pinfunction "13_13") (pintype "passive"))
      (node (ref "U$4") (pin "14") (pinfunction "14_14") (pintype "passive"))
    )
    (net (code "134") (name "OUT_48") (class "Default")
      (node (ref "IC27") (pin "13") (pinfunction "-IN_13") (pintype "input"))
      (node (ref "IC27") (pin "14") (pinfunction "OUT_14") (pintype "output"))
      (node (ref "U$4") (pin "15") (pinfunction "15_15") (pintype "passive"))
      (node (ref "U$4") (pin "16") (pinfunction "16_16") (pintype "passive"))
    )
    (net (code "135") (name "OUT_49") (class "Default")
      (node (ref "IC27") (pin "8") (pinfunction "OUT_8") (pintype "output"))
      (node (ref "IC27") (pin "9") (pinfunction "-IN_9") (pintype "input"))
      (node (ref "U$4") (pin "17") (pinfunction "17_17") (pintype "passive"))
      (node (ref "U$4") (pin "18") (pinfunction "18_18") (pintype "passive"))
    )
    (net (code "136") (name "OUT_50") (class "Default")
      (node (ref "IC27") (pin "6") (pinfunction "-IN_6") (pintype "input"))
      (node (ref "IC27") (pin "7") (pinfunction "OUT_7") (pintype "output"))
      (node (ref "U$4") (pin "19") (pinfunction "19_19") (pintype "passive"))
      (node (ref "U$4") (pin "20") (pinfunction "20_20") (pintype "passive"))
    )
    (net (code "137") (name "OUT_51") (class "Default")
      (node (ref "IC27") (pin "1") (pinfunction "OUT_1") (pintype "output"))
      (node (ref "IC27") (pin "2") (pinfunction "-IN_2") (pintype "input"))
      (node (ref "U$4") (pin "21") (pinfunction "21_21") (pintype "passive"))
      (node (ref "U$4") (pin "22") (pinfunction "22_22") (pintype "passive"))
    )
    (net (code "138") (name "OUT_52") (class "Default")
      (node (ref "IC28") (pin "13") (pinfunction "-IN_13") (pintype "input"))
      (node (ref "IC28") (pin "14") (pinfunction "OUT_14") (pintype "output"))
      (node (ref "U$4") (pin "23") (pinfunction "23_23") (pintype "passive"))
      (node (ref "U$4") (pin "24") (pinfunction "24_24") (pintype "passive"))
    )
    (net (code "139") (name "OUT_53") (class "Default")
      (node (ref "IC28") (pin "8") (pinfunction "OUT_8") (pintype "output"))
      (node (ref "IC28") (pin "9") (pinfunction "-IN_9") (pintype "input"))
      (node (ref "U$4") (pin "25") (pinfunction "25_25") (pintype "passive"))
      (node (ref "U$4") (pin "26") (pinfunction "26_26") (pintype "passive"))
    )
    (net (code "140") (name "OUT_54") (class "Default")
      (node (ref "IC28") (pin "6") (pinfunction "-IN_6") (pintype "input"))
      (node (ref "IC28") (pin "7") (pinfunction "OUT_7") (pintype "output"))
      (node (ref "U$4") (pin "27") (pinfunction "27_27") (pintype "passive"))
      (node (ref "U$4") (pin "28") (pinfunction "28_28") (pintype "passive"))
    )
    (net (code "141") (name "OUT_55") (class "Default")
      (node (ref "IC28") (pin "1") (pinfunction "OUT_1") (pintype "output"))
      (node (ref "IC28") (pin "2") (pinfunction "-IN_2") (pintype "input"))
      (node (ref "U$4") (pin "29") (pinfunction "29_29") (pintype "passive"))
      (node (ref "U$4") (pin "30") (pinfunction "30_30") (pintype "passive"))
    )
    (net (code "142") (name "SCK") (class "Default")
      (node (ref "IC2") (pin "10") (pinfunction "SCLK_10") (pintype "bidirectional"))
      (node (ref "X6") (pin "7") (pinfunction "7_7") (pintype "passive"))
    )
    (net (code "143") (name "SDA") (class "Default")
      (node (ref "IC2") (pin "11") (pinfunction "DIN_11") (pintype "bidirectional"))
      (node (ref "X6") (pin "8") (pinfunction "8_8") (pintype "passive"))
    )
    (net (code "144") (name "unconnected-(X6-Pad5)") (class "Default")
      (node (ref "X6") (pin "5") (pinfunction "5_5") (pintype "passive"))
    )
    (net (code "145") (name "unconnected-(X6-Pad12)") (class "Default")
      (node (ref "X6") (pin "12") (pinfunction "12_12") (pintype "passive"))
    )
    (net (code "146") (name "unconnected-(X6-Pad13)") (class "Default")
      (node (ref "X6") (pin "13") (pinfunction "13_13") (pintype "passive"))
    )
    (net (code "147") (name "~{SYNC}") (class "Default")
      (node (ref "IC2") (pin "9") (pinfunction "~{SYNC}_9") (pintype "bidirectional"))
      (node (ref "X6") (pin "10") (pinfunction "10_10") (pintype "passive"))
    )
  )
)
